# WT_ControlBoard.net
KiCad netlist of a schematic drawn in EAGLE
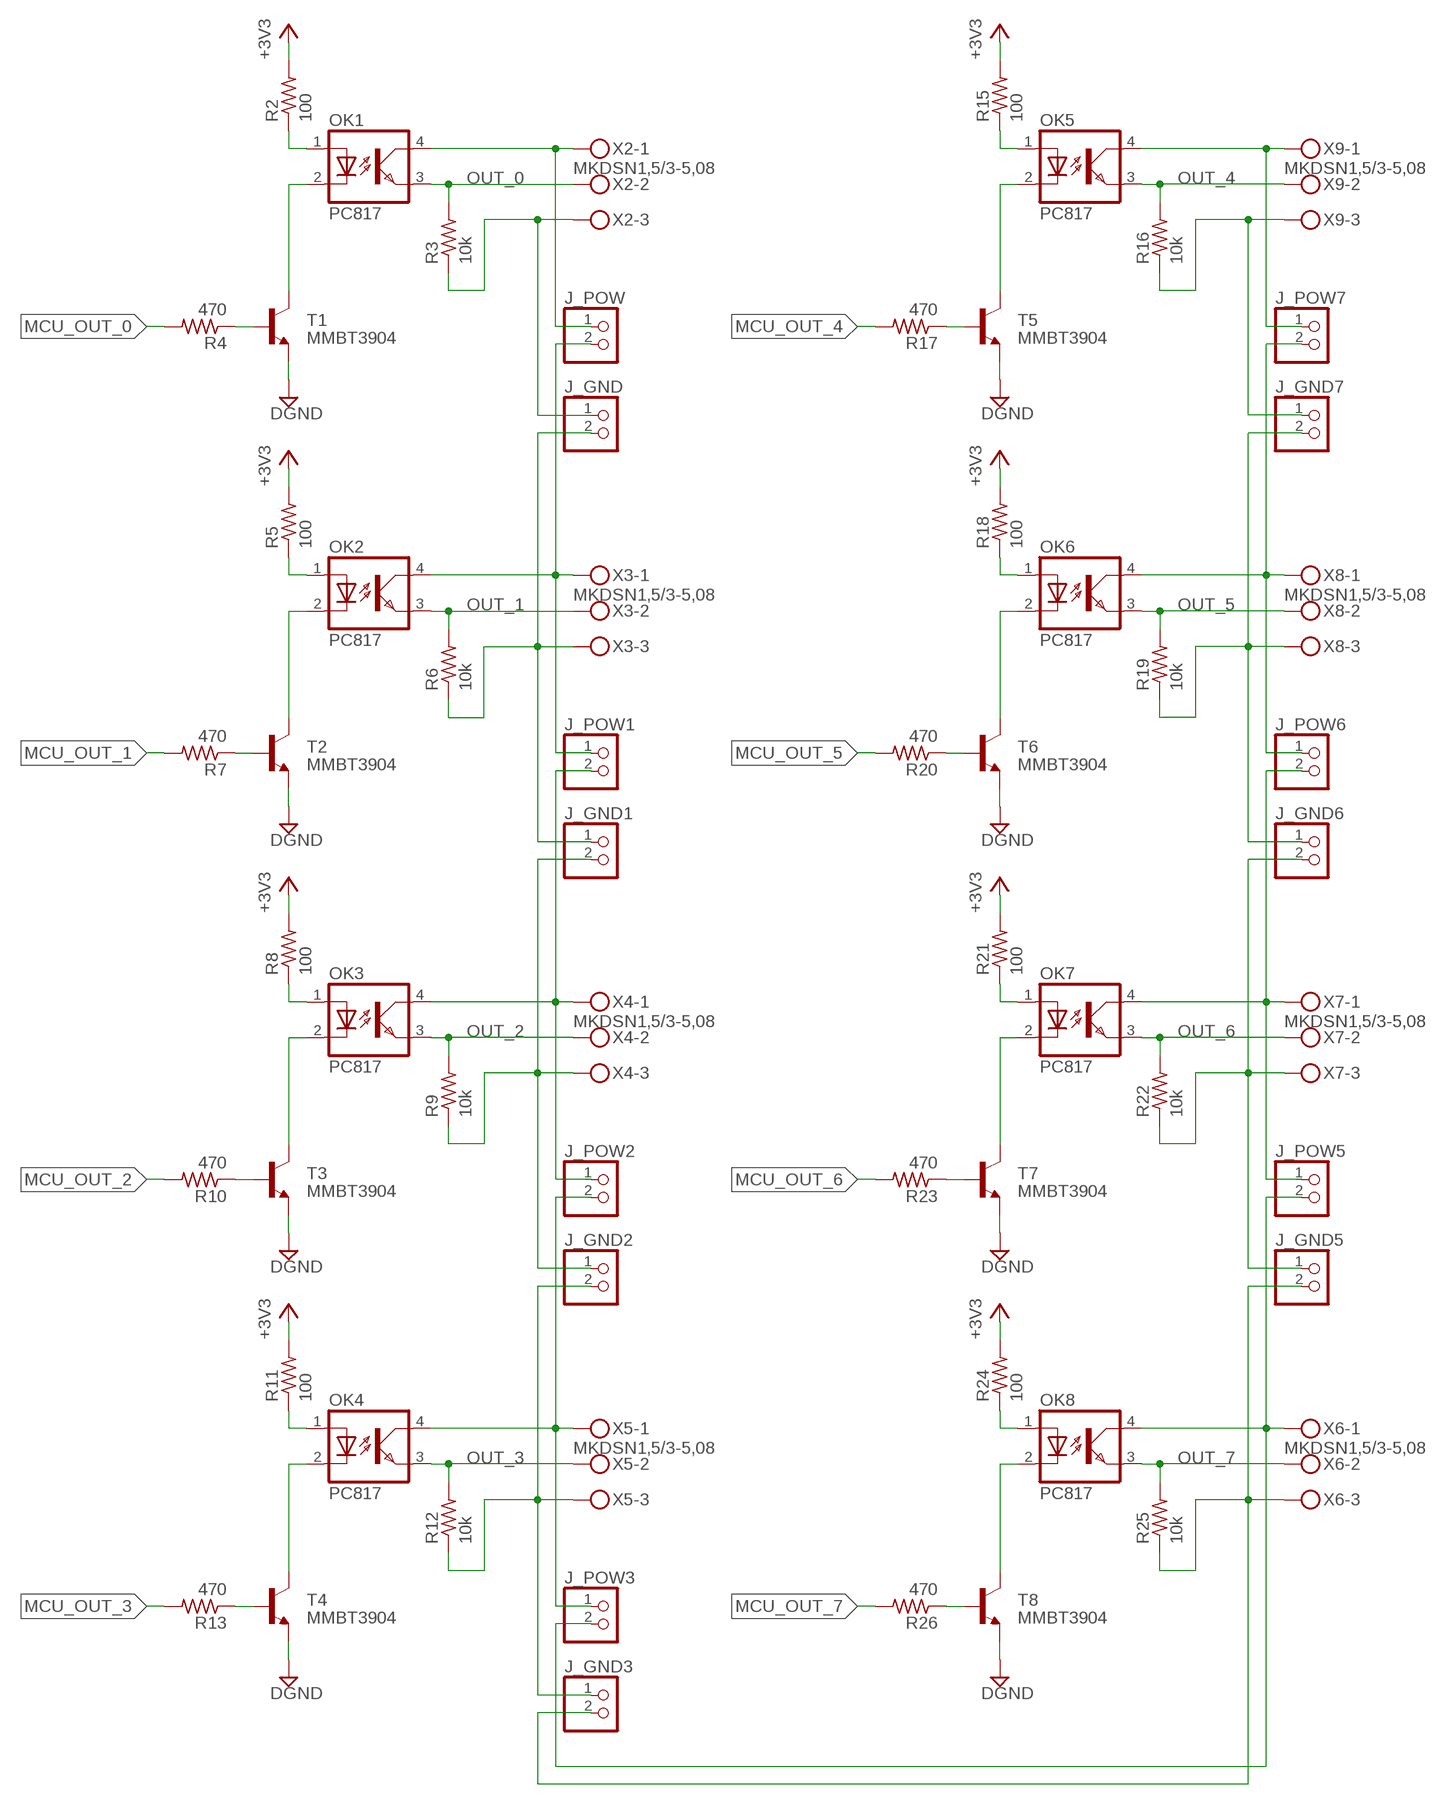
[diagram p0: schematic, sheet 1]
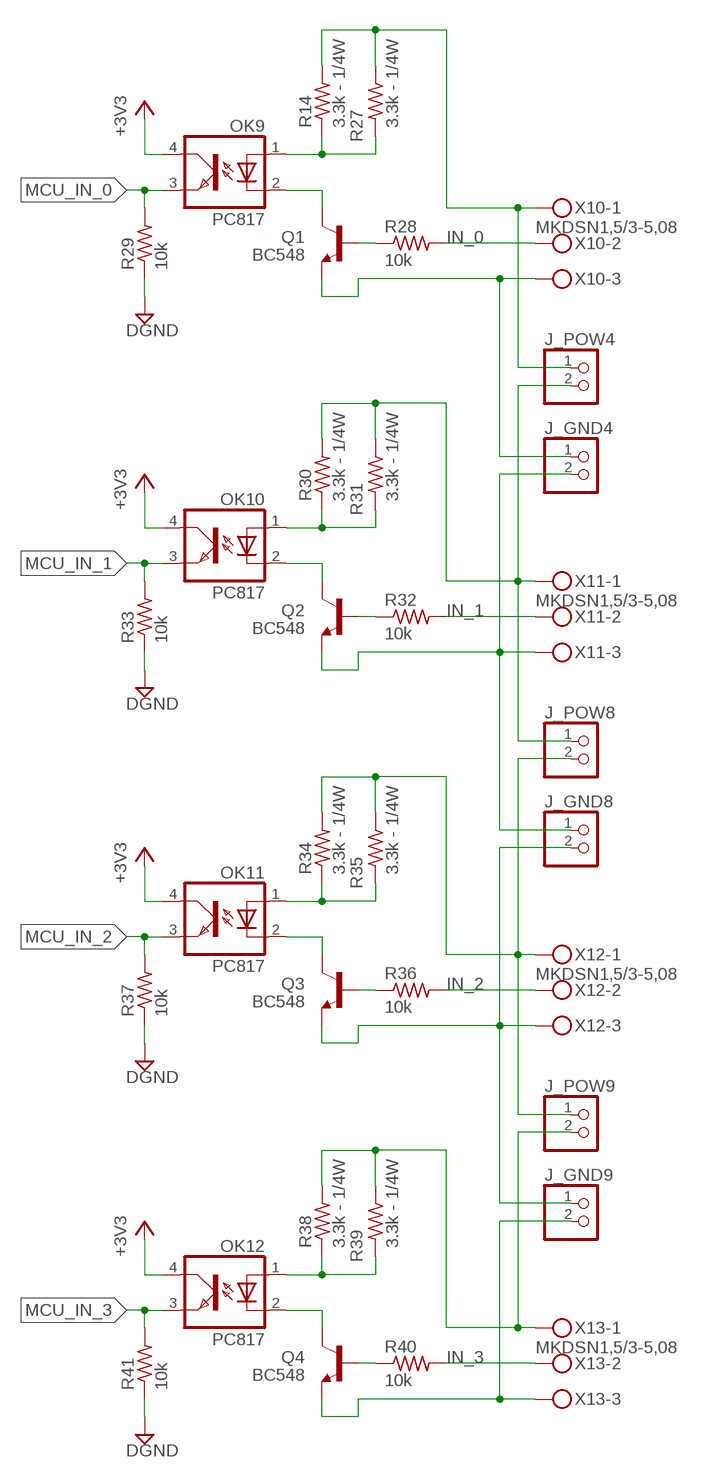
[diagram p1: schematic, sheet 2]
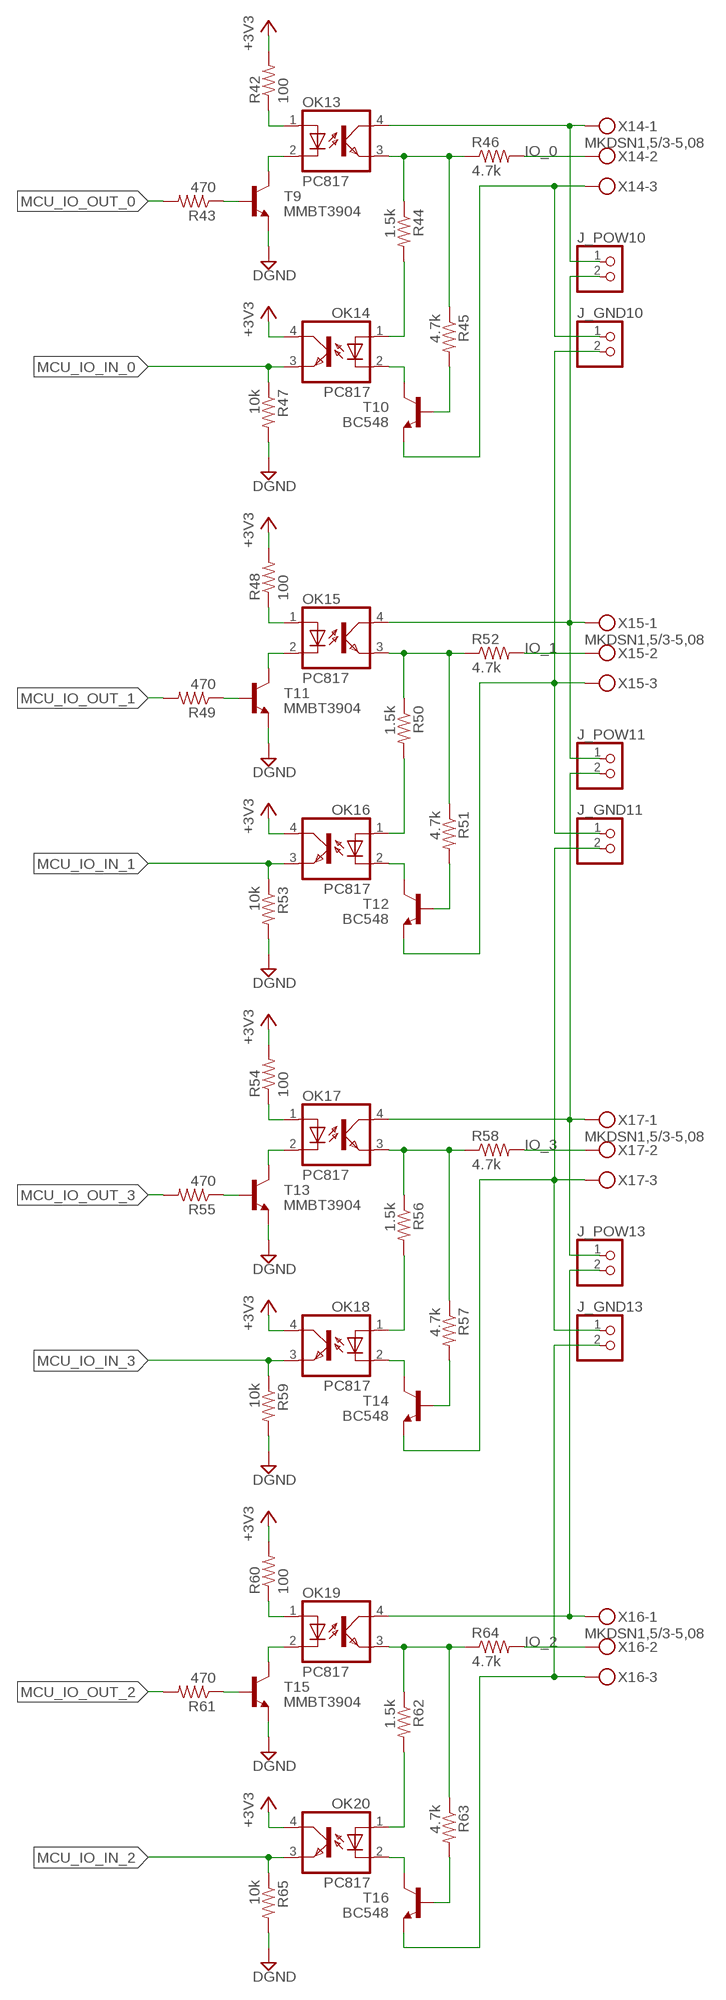
[diagram p2: schematic, sheet 3]
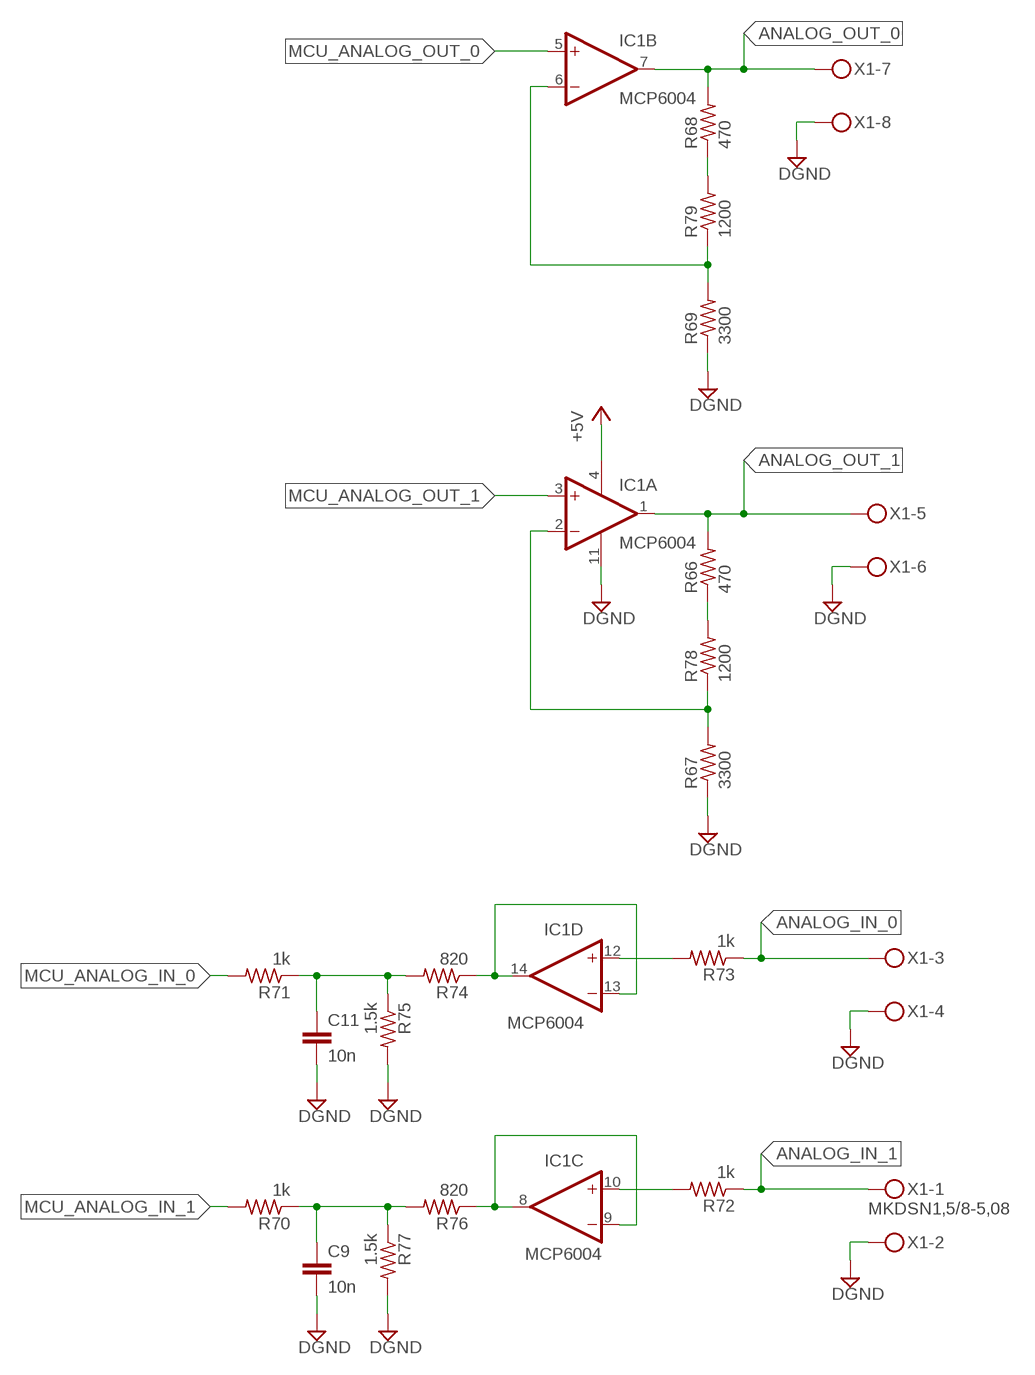
[diagram p3: schematic, sheet 4]
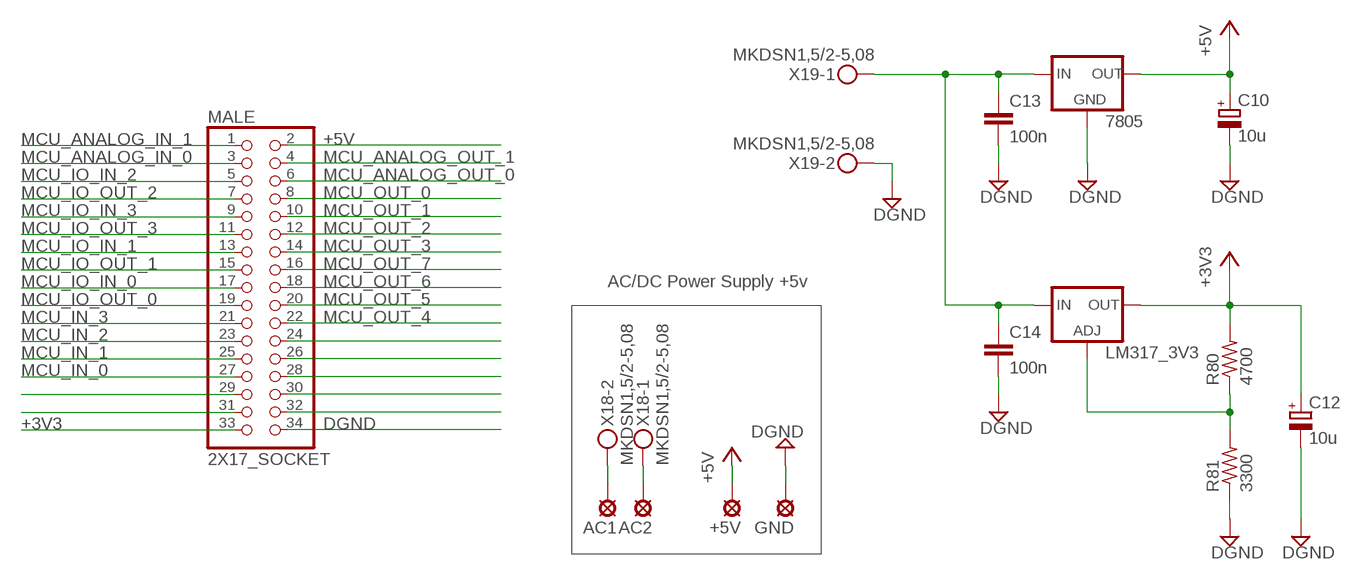
[diagram p4: schematic, sheet 5]

(export (version "E")
  (design (tool "Eeschema 10.0.6"))
  (components
    (comp (ref "+5V")
      (value "LSP10")
      (footprint "eagle-import:LSP10")
      (libsource (lib "eagle-import") (part "LSP10"))
    )
    (comp (ref "7805")
      (value "78XXS")
      (footprint "eagle-import:78XXS")
      (libsource (lib "eagle-import") (part "78XXS"))
    )
    (comp (ref "AC1")
      (value "LSP10")
      (footprint "eagle-import:LSP10")
      (libsource (lib "eagle-import") (part "LSP10"))
    )
    (comp (ref "AC2")
      (value "LSP10")
      (footprint "eagle-import:LSP10")
      (libsource (lib "eagle-import") (part "LSP10"))
    )
    (comp (ref "C10")
      (value "10u")
      (footprint "eagle-import:E1,8-4")
      (libsource (lib "eagle-import") (part "CPOL-EUE1.8-4"))
    )
    (comp (ref "C12")
      (value "10u")
      (footprint "eagle-import:E1,8-4")
      (libsource (lib "eagle-import") (part "CPOL-EUE1.8-4"))
    )
    (comp (ref "C13")
      (value "100n")
      (footprint "eagle-import:C1206")
      (libsource (lib "eagle-import") (part "C-EUC1206"))
    )
    (comp (ref "C14")
      (value "100n")
      (footprint "eagle-import:C1206")
      (libsource (lib "eagle-import") (part "C-EUC1206"))
    )
    (comp (ref "GND")
      (value "LSP10")
      (footprint "eagle-import:LSP10")
      (libsource (lib "eagle-import") (part "LSP10"))
    )
    (comp (ref "LM317_3V3")
      (value "LM317TS")
      (footprint "eagle-import:317TS")
      (libsource (lib "eagle-import") (part "LM317TS"))
    )
    (comp (ref "MALE")
      (value "2X17_SOCKET")
      (footprint "eagle-import:2X17_SOCKET")
      (libsource (lib "eagle-import") (part "2X17_SOCKET"))
    )
    (comp (ref "R80")
      (value "4700")
      (footprint "eagle-import:0204V")
      (libsource (lib "eagle-import") (part "R-US_0204/2V"))
    )
    (comp (ref "R81")
      (value "3300")
      (footprint "eagle-import:0204V")
      (libsource (lib "eagle-import") (part "R-US_0204/2V"))
    )
    (comp (ref "X18")
      (value "MKDSN1,5/2-5,08")
      (footprint "eagle-import:MKDSN1,5_2-5,08")
      (libsource (lib "eagle-import") (part "MKDSN1,5/2-5,08"))
    )
    (comp (ref "X19")
      (value "MKDSN1,5/2-5,08")
      (footprint "eagle-import:MKDSN1,5_2-5,08")
      (libsource (lib "eagle-import") (part "MKDSN1,5/2-5,08"))
    )
    (comp (ref "C9")
      (value "10n")
      (footprint "eagle-import:C0402")
      (libsource (lib "eagle-import") (part "C-EUC0402"))
    )
    (comp (ref "C11")
      (value "10n")
      (footprint "eagle-import:C0402")
      (libsource (lib "eagle-import") (part "C-EUC0402"))
    )
    (comp (ref "IC1")
      (value "MCP6004")
      (footprint "eagle-import:SO14")
      (libsource (lib "eagle-import") (part "LM324D"))
    )
    (comp (ref "R66")
      (value "470")
      (footprint "eagle-import:R0402")
      (libsource (lib "eagle-import") (part "R-US_R0402"))
    )
    (comp (ref "R67")
      (value "3300")
      (footprint "eagle-import:R0402")
      (libsource (lib "eagle-import") (part "R-US_R0402"))
    )
    (comp (ref "R68")
      (value "470")
      (footprint "eagle-import:R0402")
      (libsource (lib "eagle-import") (part "R-US_R0402"))
    )
    (comp (ref "R69")
      (value "3300")
      (footprint "eagle-import:R0402")
      (libsource (lib "eagle-import") (part "R-US_R0402"))
    )
    (comp (ref "R70")
      (value "1k")
      (footprint "eagle-import:R0402")
      (libsource (lib "eagle-import") (part "R-US_R0402"))
    )
    (comp (ref "R71")
      (value "1k")
      (footprint "eagle-import:R0402")
      (libsource (lib "eagle-import") (part "R-US_R0402"))
    )
    (comp (ref "R72")
      (value "1k")
      (footprint "eagle-import:0204V")
      (libsource (lib "eagle-import") (part "R-US_0204/2V"))
    )
    (comp (ref "R73")
      (value "1k")
      (footprint "eagle-import:0204_7")
      (libsource (lib "eagle-import") (part "R-US_0204/7"))
    )
    (comp (ref "R74")
      (value "820")
      (footprint "eagle-import:R0402")
      (libsource (lib "eagle-import") (part "R-US_R0402"))
    )
    (comp (ref "R75")
      (value "1.5k")
      (footprint "eagle-import:R0402")
      (libsource (lib "eagle-import") (part "R-US_R0402"))
    )
    (comp (ref "R76")
      (value "820")
      (footprint "eagle-import:R0402")
      (libsource (lib "eagle-import") (part "R-US_R0402"))
    )
    (comp (ref "R77")
      (value "1.5k")
      (footprint "eagle-import:R0402")
      (libsource (lib "eagle-import") (part "R-US_R0402"))
    )
    (comp (ref "R78")
      (value "1200")
      (footprint "eagle-import:R0402")
      (libsource (lib "eagle-import") (part "R-US_R0402"))
    )
    (comp (ref "R79")
      (value "1200")
      (footprint "eagle-import:R0402")
      (libsource (lib "eagle-import") (part "R-US_R0402"))
    )
    (comp (ref "X1")
      (value "MKDSN1,5/8-5,08")
      (footprint "eagle-import:MKDSN1,5_8-5,08")
      (libsource (lib "eagle-import") (part "MKDSN1,5/8-5,08"))
    )
    (comp (ref "J_GND4")
      (value "PINHD-1X2")
      (footprint "eagle-import:1X02")
      (libsource (lib "eagle-import") (part "PINHD-1X2"))
    )
    (comp (ref "J_GND8")
      (value "PINHD-1X2")
      (footprint "eagle-import:1X02")
      (libsource (lib "eagle-import") (part "PINHD-1X2"))
    )
    (comp (ref "J_GND9")
      (value "PINHD-1X2")
      (footprint "eagle-import:1X02")
      (libsource (lib "eagle-import") (part "PINHD-1X2"))
    )
    (comp (ref "J_POW4")
      (value "PINHD-1X2")
      (footprint "eagle-import:1X02")
      (libsource (lib "eagle-import") (part "PINHD-1X2"))
    )
    (comp (ref "J_POW8")
      (value "PINHD-1X2")
      (footprint "eagle-import:1X02")
      (libsource (lib "eagle-import") (part "PINHD-1X2"))
    )
    (comp (ref "J_POW9")
      (value "PINHD-1X2")
      (footprint "eagle-import:1X02")
      (libsource (lib "eagle-import") (part "PINHD-1X2"))
    )
    (comp (ref "OK9")
      (value "PC817")
      (footprint "eagle-import:DIL04")
      (fields (field (name "MPN") "PC817X4J000F"))
      (libsource (lib "eagle-import") (part "PC817"))
    )
    (comp (ref "OK10")
      (value "PC817")
      (footprint "eagle-import:DIL04")
      (fields (field (name "MPN") "PC817X4J000F"))
      (libsource (lib "eagle-import") (part "PC817"))
    )
    (comp (ref "OK11")
      (value "PC817")
      (footprint "eagle-import:DIL04")
      (fields (field (name "MPN") "PC817X4J000F"))
      (libsource (lib "eagle-import") (part "PC817"))
    )
    (comp (ref "OK12")
      (value "PC817")
      (footprint "eagle-import:DIL04")
      (fields (field (name "MPN") "PC817X4J000F"))
      (libsource (lib "eagle-import") (part "PC817"))
    )
    (comp (ref "Q1")
      (value "BC548")
      (footprint "eagle-import:TO92-EBC")
      (libsource (lib "eagle-import") (part "BC548"))
    )
    (comp (ref "Q2")
      (value "BC548")
      (footprint "eagle-import:TO92-EBC")
      (libsource (lib "eagle-import") (part "BC548"))
    )
    (comp (ref "Q3")
      (value "BC548")
      (footprint "eagle-import:TO92-EBC")
      (libsource (lib "eagle-import") (part "BC548"))
    )
    (comp (ref "Q4")
      (value "BC548")
      (footprint "eagle-import:TO92-EBC")
      (libsource (lib "eagle-import") (part "BC548"))
    )
    (comp (ref "R14")
      (value "3.3k - 1/4W")
      (footprint "eagle-import:0204V")
      (libsource (lib "eagle-import") (part "R-US_0204/2V"))
    )
    (comp (ref "R27")
      (value "3.3k - 1/4W")
      (footprint "eagle-import:0204V")
      (libsource (lib "eagle-import") (part "R-US_0204/2V"))
    )
    (comp (ref "R28")
      (value "10k")
      (footprint "eagle-import:0204_5")
      (libsource (lib "eagle-import") (part "R-US_0204/5"))
    )
    (comp (ref "R29")
      (value "10k")
      (footprint "eagle-import:R0402")
      (libsource (lib "eagle-import") (part "R-US_R0402"))
    )
    (comp (ref "R30")
      (value "3.3k - 1/4W")
      (footprint "eagle-import:0204V")
      (libsource (lib "eagle-import") (part "R-US_0204/2V"))
    )
    (comp (ref "R31")
      (value "3.3k - 1/4W")
      (footprint "eagle-import:0204V")
      (libsource (lib "eagle-import") (part "R-US_0204/2V"))
    )
    (comp (ref "R32")
      (value "10k")
      (footprint "eagle-import:0204_5")
      (libsource (lib "eagle-import") (part "R-US_0204/5"))
    )
    (comp (ref "R33")
      (value "10k")
      (footprint "eagle-import:R0402")
      (libsource (lib "eagle-import") (part "R-US_R0402"))
    )
    (comp (ref "R34")
      (value "3.3k - 1/4W")
      (footprint "eagle-import:0204V")
      (libsource (lib "eagle-import") (part "R-US_0204/2V"))
    )
    (comp (ref "R35")
      (value "3.3k - 1/4W")
      (footprint "eagle-import:0204V")
      (libsource (lib "eagle-import") (part "R-US_0204/2V"))
    )
    (comp (ref "R36")
      (value "10k")
      (footprint "eagle-import:0204_5")
      (libsource (lib "eagle-import") (part "R-US_0204/5"))
    )
    (comp (ref "R37")
      (value "10k")
      (footprint "eagle-import:R0402")
      (libsource (lib "eagle-import") (part "R-US_R0402"))
    )
    (comp (ref "R38")
      (value "3.3k - 1/4W")
      (footprint "eagle-import:0204V")
      (libsource (lib "eagle-import") (part "R-US_0204/2V"))
    )
    (comp (ref "R39")
      (value "3.3k - 1/4W")
      (footprint "eagle-import:0204V")
      (libsource (lib "eagle-import") (part "R-US_0204/2V"))
    )
    (comp (ref "R40")
      (value "10k")
      (footprint "eagle-import:0204_5")
      (libsource (lib "eagle-import") (part "R-US_0204/5"))
    )
    (comp (ref "R41")
      (value "10k")
      (footprint "eagle-import:R0402")
      (libsource (lib "eagle-import") (part "R-US_R0402"))
    )
    (comp (ref "X10")
      (value "MKDSN1,5/3-5,08")
      (footprint "eagle-import:MKDSN1,5_3-5,08")
      (libsource (lib "eagle-import") (part "MKDSN1,5/3-5,08"))
    )
    (comp (ref "X11")
      (value "MKDSN1,5/3-5,08")
      (footprint "eagle-import:MKDSN1,5_3-5,08")
      (libsource (lib "eagle-import") (part "MKDSN1,5/3-5,08"))
    )
    (comp (ref "X12")
      (value "MKDSN1,5/3-5,08")
      (footprint "eagle-import:MKDSN1,5_3-5,08")
      (libsource (lib "eagle-import") (part "MKDSN1,5/3-5,08"))
    )
    (comp (ref "X13")
      (value "MKDSN1,5/3-5,08")
      (footprint "eagle-import:MKDSN1,5_3-5,08")
      (libsource (lib "eagle-import") (part "MKDSN1,5/3-5,08"))
    )
    (comp (ref "J_GND")
      (value "PINHD-1X2")
      (footprint "eagle-import:1X02")
      (libsource (lib "eagle-import") (part "PINHD-1X2"))
    )
    (comp (ref "J_GND1")
      (value "PINHD-1X2")
      (footprint "eagle-import:1X02")
      (libsource (lib "eagle-import") (part "PINHD-1X2"))
    )
    (comp (ref "J_GND2")
      (value "PINHD-1X2")
      (footprint "eagle-import:1X02")
      (libsource (lib "eagle-import") (part "PINHD-1X2"))
    )
    (comp (ref "J_GND3")
      (value "PINHD-1X2")
      (footprint "eagle-import:1X02")
      (libsource (lib "eagle-import") (part "PINHD-1X2"))
    )
    (comp (ref "J_GND5")
      (value "PINHD-1X2")
      (footprint "eagle-import:1X02")
      (libsource (lib "eagle-import") (part "PINHD-1X2"))
    )
    (comp (ref "J_GND6")
      (value "PINHD-1X2")
      (footprint "eagle-import:1X02")
      (libsource (lib "eagle-import") (part "PINHD-1X2"))
    )
    (comp (ref "J_GND7")
      (value "PINHD-1X2")
      (footprint "eagle-import:1X02")
      (libsource (lib "eagle-import") (part "PINHD-1X2"))
    )
    (comp (ref "J_POW")
      (value "PINHD-1X2")
      (footprint "eagle-import:1X02")
      (libsource (lib "eagle-import") (part "PINHD-1X2"))
    )
    (comp (ref "J_POW1")
      (value "PINHD-1X2")
      (footprint "eagle-import:1X02")
      (libsource (lib "eagle-import") (part "PINHD-1X2"))
    )
    (comp (ref "J_POW2")
      (value "PINHD-1X2")
      (footprint "eagle-import:1X02")
      (libsource (lib "eagle-import") (part "PINHD-1X2"))
    )
    (comp (ref "J_POW3")
      (value "PINHD-1X2")
      (footprint "eagle-import:1X02")
      (libsource (lib "eagle-import") (part "PINHD-1X2"))
    )
    (comp (ref "J_POW5")
      (value "PINHD-1X2")
      (footprint "eagle-import:1X02")
      (libsource (lib "eagle-import") (part "PINHD-1X2"))
    )
    (comp (ref "J_POW6")
      (value "PINHD-1X2")
      (footprint "eagle-import:1X02")
      (libsource (lib "eagle-import") (part "PINHD-1X2"))
    )
    (comp (ref "J_POW7")
      (value "PINHD-1X2")
      (footprint "eagle-import:1X02")
      (libsource (lib "eagle-import") (part "PINHD-1X2"))
    )
    (comp (ref "OK1")
      (value "PC817")
      (footprint "eagle-import:DIL04")
      (fields (field (name "MPN") "PC817X4J000F"))
      (libsource (lib "eagle-import") (part "PC817"))
    )
    (comp (ref "OK2")
      (value "PC817")
      (footprint "eagle-import:DIL04")
      (fields (field (name "MPN") "PC817X4J000F"))
      (libsource (lib "eagle-import") (part "PC817"))
    )
    (comp (ref "OK3")
      (value "PC817")
      (footprint "eagle-import:DIL04")
      (fields (field (name "MPN") "PC817X4J000F"))
      (libsource (lib "eagle-import") (part "PC817"))
    )
    (comp (ref "OK4")
      (value "PC817")
      (footprint "eagle-import:DIL04")
      (fields (field (name "MPN") "PC817X4J000F"))
      (libsource (lib "eagle-import") (part "PC817"))
    )
    (comp (ref "OK5")
      (value "PC817")
      (footprint "eagle-import:DIL04")
      (fields (field (name "MPN") "PC817X4J000F"))
      (libsource (lib "eagle-import") (part "PC817"))
    )
    (comp (ref "OK6")
      (value "PC817")
      (footprint "eagle-import:DIL04")
      (fields (field (name "MPN") "PC817X4J000F"))
      (libsource (lib "eagle-import") (part "PC817"))
    )
    (comp (ref "OK7")
      (value "PC817")
      (footprint "eagle-import:DIL04")
      (fields (field (name "MPN") "PC817X4J000F"))
      (libsource (lib "eagle-import") (part "PC817"))
    )
    (comp (ref "OK8")
      (value "PC817")
      (footprint "eagle-import:DIL04")
      (fields (field (name "MPN") "PC817X4J000F"))
      (libsource (lib "eagle-import") (part "PC817"))
    )
    (comp (ref "R2")
      (value "100")
      (footprint "eagle-import:R0402")
      (libsource (lib "eagle-import") (part "R-US_R0402"))
    )
    (comp (ref "R3")
      (value "10k")
      (footprint "eagle-import:R0402")
      (libsource (lib "eagle-import") (part "R-US_R0402"))
    )
    (comp (ref "R4")
      (value "470")
      (footprint "eagle-import:0204_5")
      (libsource (lib "eagle-import") (part "R-US_0204/5"))
    )
    (comp (ref "R5")
      (value "100")
      (footprint "eagle-import:R0402")
      (libsource (lib "eagle-import") (part "R-US_R0402"))
    )
    (comp (ref "R6")
      (value "10k")
      (footprint "eagle-import:R0402")
      (libsource (lib "eagle-import") (part "R-US_R0402"))
    )
    (comp (ref "R7")
      (value "470")
      (footprint "eagle-import:0204_5")
      (libsource (lib "eagle-import") (part "R-US_0204/5"))
    )
    (comp (ref "R8")
      (value "100")
      (footprint "eagle-import:R0402")
      (libsource (lib "eagle-import") (part "R-US_R0402"))
    )
    (comp (ref "R9")
      (value "10k")
      (footprint "eagle-import:R0402")
      (libsource (lib "eagle-import") (part "R-US_R0402"))
    )
    (comp (ref "R10")
      (value "470")
      (footprint "eagle-import:0204_5")
      (libsource (lib "eagle-import") (part "R-US_0204/5"))
    )
    (comp (ref "R11")
      (value "100")
      (footprint "eagle-import:R0402")
      (libsource (lib "eagle-import") (part "R-US_R0402"))
    )
    (comp (ref "R12")
      (value "10k")
      (footprint "eagle-import:R0402")
      (libsource (lib "eagle-import") (part "R-US_R0402"))
    )
    (comp (ref "R13")
      (value "470")
      (footprint "eagle-import:0204_5")
      (libsource (lib "eagle-import") (part "R-US_0204/5"))
    )
    (comp (ref "R15")
      (value "100")
      (footprint "eagle-import:R0402")
      (libsource (lib "eagle-import") (part "R-US_R0402"))
    )
    (comp (ref "R16")
      (value "10k")
      (footprint "eagle-import:R0402")
      (libsource (lib "eagle-import") (part "R-US_R0402"))
    )
    (comp (ref "R17")
      (value "470")
      (footprint "eagle-import:0204_7")
      (libsource (lib "eagle-import") (part "R-US_0204/7"))
    )
    (comp (ref "R18")
      (value "100")
      (footprint "eagle-import:R0402")
      (libsource (lib "eagle-import") (part "R-US_R0402"))
    )
    (comp (ref "R19")
      (value "10k")
      (footprint "eagle-import:R0402")
      (libsource (lib "eagle-import") (part "R-US_R0402"))
    )
    (comp (ref "R20")
      (value "470")
      (footprint "eagle-import:0204_5")
      (libsource (lib "eagle-import") (part "R-US_0204/5"))
    )
    (comp (ref "R21")
      (value "100")
      (footprint "eagle-import:R0402")
      (libsource (lib "eagle-import") (part "R-US_R0402"))
    )
    (comp (ref "R22")
      (value "10k")
      (footprint "eagle-import:R0402")
      (libsource (lib "eagle-import") (part "R-US_R0402"))
    )
    (comp (ref "R23")
      (value "470")
      (footprint "eagle-import:0204_5")
      (libsource (lib "eagle-import") (part "R-US_0204/5"))
    )
    (comp (ref "R24")
      (value "100")
      (footprint "eagle-import:R0402")
      (libsource (lib "eagle-import") (part "R-US_R0402"))
    )
    (comp (ref "R25")
      (value "10k")
      (footprint "eagle-import:R0402")
      (libsource (lib "eagle-import") (part "R-US_R0402"))
    )
    (comp (ref "R26")
      (value "470")
      (footprint "eagle-import:0204_5")
      (libsource (lib "eagle-import") (part "R-US_0204/5"))
    )
    (comp (ref "T1")
      (value "MMBT3904")
      (footprint "eagle-import:SOT23-BEC")
      (libsource (lib "eagle-import") (part "-NPN-SOT23-BECMMBT3904LT1"))
    )
    (comp (ref "T2")
      (value "MMBT3904")
      (footprint "eagle-import:SOT23-BEC")
      (libsource (lib "eagle-import") (part "-NPN-SOT23-BECMMBT3904LT1"))
    )
    (comp (ref "T3")
      (value "MMBT3904")
      (footprint "eagle-import:SOT23-BEC")
      (libsource (lib "eagle-import") (part "-NPN-SOT23-BECMMBT3904LT1"))
    )
    (comp (ref "T4")
      (value "MMBT3904")
      (footprint "eagle-import:SOT23-BEC")
      (libsource (lib "eagle-import") (part "-NPN-SOT23-BECMMBT3904LT1"))
    )
    (comp (ref "T5")
      (value "MMBT3904")
      (footprint "eagle-import:SOT23-BEC")
      (libsource (lib "eagle-import") (part "-NPN-SOT23-BECMMBT3904LT1"))
    )
    (comp (ref "T6")
      (value "MMBT3904")
      (footprint "eagle-import:SOT23-BEC")
      (libsource (lib "eagle-import") (part "-NPN-SOT23-BECMMBT3904LT1"))
    )
    (comp (ref "T7")
      (value "MMBT3904")
      (footprint "eagle-import:SOT23-BEC")
      (libsource (lib "eagle-import") (part "-NPN-SOT23-BECMMBT3904LT1"))
    )
    (comp (ref "T8")
      (value "MMBT3904")
      (footprint "eagle-import:SOT23-BEC")
      (libsource (lib "eagle-import") (part "-NPN-SOT23-BECMMBT3904LT1"))
    )
    (comp (ref "X2")
      (value "MKDSN1,5/3-5,08")
      (footprint "eagle-import:MKDSN1,5_3-5,08")
      (libsource (lib "eagle-import") (part "MKDSN1,5/3-5,08"))
    )
    (comp (ref "X3")
      (value "MKDSN1,5/3-5,08")
      (footprint "eagle-import:MKDSN1,5_3-5,08")
      (libsource (lib "eagle-import") (part "MKDSN1,5/3-5,08"))
    )
    (comp (ref "X4")
      (value "MKDSN1,5/3-5,08")
      (footprint "eagle-import:MKDSN1,5_3-5,08")
      (libsource (lib "eagle-import") (part "MKDSN1,5/3-5,08"))
    )
    (comp (ref "X5")
      (value "MKDSN1,5/3-5,08")
      (footprint "eagle-import:MKDSN1,5_3-5,08")
      (libsource (lib "eagle-import") (part "MKDSN1,5/3-5,08"))
    )
    (comp (ref "X6")
      (value "MKDSN1,5/3-5,08")
      (footprint "eagle-import:MKDSN1,5_3-5,08")
      (libsource (lib "eagle-import") (part "MKDSN1,5/3-5,08"))
    )
    (comp (ref "X7")
      (value "MKDSN1,5/3-5,08")
      (footprint "eagle-import:MKDSN1,5_3-5,08")
      (libsource (lib "eagle-import") (part "MKDSN1,5/3-5,08"))
    )
    (comp (ref "X8")
      (value "MKDSN1,5/3-5,08")
      (footprint "eagle-import:MKDSN1,5_3-5,08")
      (libsource (lib "eagle-import") (part "MKDSN1,5/3-5,08"))
    )
    (comp (ref "X9")
      (value "MKDSN1,5/3-5,08")
      (footprint "eagle-import:MKDSN1,5_3-5,08")
      (libsource (lib "eagle-import") (part "MKDSN1,5/3-5,08"))
    )
    (comp (ref "J_GND10")
      (value "PINHD-1X2")
      (footprint "eagle-import:1X02")
      (libsource (lib "eagle-import") (part "PINHD-1X2"))
    )
    (comp (ref "J_GND11")
      (value "PINHD-1X2")
      (footprint "eagle-import:1X02")
      (libsource (lib "eagle-import") (part "PINHD-1X2"))
    )
    (comp (ref "J_GND13")
      (value "PINHD-1X2")
      (footprint "eagle-import:1X02")
      (libsource (lib "eagle-import") (part "PINHD-1X2"))
    )
    (comp (ref "J_POW10")
      (value "PINHD-1X2")
      (footprint "eagle-import:1X02")
      (libsource (lib "eagle-import") (part "PINHD-1X2"))
    )
    (comp (ref "J_POW11")
      (value "PINHD-1X2")
      (footprint "eagle-import:1X02")
      (libsource (lib "eagle-import") (part "PINHD-1X2"))
    )
    (comp (ref "J_POW13")
      (value "PINHD-1X2")
      (footprint "eagle-import:1X02")
      (libsource (lib "eagle-import") (part "PINHD-1X2"))
    )
    (comp (ref "OK13")
      (value "PC817")
      (footprint "eagle-import:DIL04")
      (fields (field (name "MPN") "PC817X4J000F"))
      (libsource (lib "eagle-import") (part "PC817"))
    )
    (comp (ref "OK14")
      (value "PC817")
      (footprint "eagle-import:DIL04")
      (fields (field (name "MPN") "PC817X4J000F"))
      (libsource (lib "eagle-import") (part "PC817"))
    )
    (comp (ref "OK15")
      (value "PC817")
      (footprint "eagle-import:DIL04")
      (fields (field (name "MPN") "PC817X4J000F"))
      (libsource (lib "eagle-import") (part "PC817"))
    )
    (comp (ref "OK16")
      (value "PC817")
      (footprint "eagle-import:DIL04")
      (fields (field (name "MPN") "PC817X4J000F"))
      (libsource (lib "eagle-import") (part "PC817"))
    )
    (comp (ref "OK17")
      (value "PC817")
      (footprint "eagle-import:DIL04")
      (fields (field (name "MPN") "PC817X4J000F"))
      (libsource (lib "eagle-import") (part "PC817"))
    )
    (comp (ref "OK18")
      (value "PC817")
      (footprint "eagle-import:DIL04")
      (fields (field (name "MPN") "PC817X4J000F"))
      (libsource (lib "eagle-import") (part "PC817"))
    )
    (comp (ref "OK19")
      (value "PC817")
      (footprint "eagle-import:DIL04")
      (fields (field (name "MPN") "PC817X4J000F"))
      (libsource (lib "eagle-import") (part "PC817"))
    )
    (comp (ref "OK20")
      (value "PC817")
      (footprint "eagle-import:DIL04")
      (fields (field (name "MPN") "PC817X4J000F"))
      (libsource (lib "eagle-import") (part "PC817"))
    )
    (comp (ref "R42")
      (value "100")
      (footprint "eagle-import:0204_7")
      (libsource (lib "eagle-import") (part "R-US_0204/7"))
    )
    (comp (ref "R43")
      (value "470")
      (footprint "eagle-import:R0402")
      (libsource (lib "eagle-import") (part "R-US_R0402"))
    )
    (comp (ref "R44")
      (value "1.5k")
      (footprint "eagle-import:0204_5")
      (libsource (lib "eagle-import") (part "R-US_0204/5"))
    )
    (comp (ref "R45")
      (value "4.7k")
      (footprint "eagle-import:0204V")
      (libsource (lib "eagle-import") (part "R-US_0204/2V"))
    )
    (comp (ref "R46")
      (value "4.7k")
      (footprint "eagle-import:0204V")
      (libsource (lib "eagle-import") (part "R-US_0204/2V"))
    )
    (comp (ref "R47")
      (value "10k")
      (footprint "eagle-import:0204_5")
      (libsource (lib "eagle-import") (part "R-US_0204/5"))
    )
    (comp (ref "R48")
      (value "100")
      (footprint "eagle-import:0204_7")
      (libsource (lib "eagle-import") (part "R-US_0204/7"))
    )
    (comp (ref "R49")
      (value "470")
      (footprint "eagle-import:R0402")
      (libsource (lib "eagle-import") (part "R-US_R0402"))
    )
    (comp (ref "R50")
      (value "1.5k")
      (footprint "eagle-import:0204_5")
      (libsource (lib "eagle-import") (part "R-US_0204/5"))
    )
    (comp (ref "R51")
      (value "4.7k")
      (footprint "eagle-import:0204V")
      (libsource (lib "eagle-import") (part "R-US_0204/2V"))
    )
    (comp (ref "R52")
      (value "4.7k")
      (footprint "eagle-import:0204V")
      (libsource (lib "eagle-import") (part "R-US_0204/2V"))
    )
    (comp (ref "R53")
      (value "10k")
      (footprint "eagle-import:0204_5")
      (libsource (lib "eagle-import") (part "R-US_0204/5"))
    )
    (comp (ref "R54")
      (value "100")
      (footprint "eagle-import:0204_7")
      (libsource (lib "eagle-import") (part "R-US_0204/7"))
    )
    (comp (ref "R55")
      (value "470")
      (footprint "eagle-import:R0402")
      (libsource (lib "eagle-import") (part "R-US_R0402"))
    )
    (comp (ref "R56")
      (value "1.5k")
      (footprint "eagle-import:0204_5")
      (libsource (lib "eagle-import") (part "R-US_0204/5"))
    )
    (comp (ref "R57")
      (value "4.7k")
      (footprint "eagle-import:0204V")
      (libsource (lib "eagle-import") (part "R-US_0204/2V"))
    )
    (comp (ref "R58")
      (value "4.7k")
      (footprint "eagle-import:0204V")
      (libsource (lib "eagle-import") (part "R-US_0204/2V"))
    )
    (comp (ref "R59")
      (value "10k")
      (footprint "eagle-import:0204_5")
      (libsource (lib "eagle-import") (part "R-US_0204/5"))
    )
    (comp (ref "R60")
      (value "100")
      (footprint "eagle-import:0204_7")
      (libsource (lib "eagle-import") (part "R-US_0204/7"))
    )
    (comp (ref "R61")
      (value "470")
      (footprint "eagle-import:R0402")
      (libsource (lib "eagle-import") (part "R-US_R0402"))
    )
    (comp (ref "R62")
      (value "1.5k")
      (footprint "eagle-import:0204_5")
      (libsource (lib "eagle-import") (part "R-US_0204/5"))
    )
    (comp (ref "R63")
      (value "4.7k")
      (footprint "eagle-import:0204V")
      (libsource (lib "eagle-import") (part "R-US_0204/2V"))
    )
    (comp (ref "R64")
      (value "4.7k")
      (footprint "eagle-import:0204V")
      (libsource (lib "eagle-import") (part "R-US_0204/2V"))
    )
    (comp (ref "R65")
      (value "10k")
      (footprint "eagle-import:0204_5")
      (libsource (lib "eagle-import") (part "R-US_0204/5"))
    )
    (comp (ref "T9")
      (value "MMBT3904")
      (footprint "eagle-import:SOT23-BEC")
      (libsource (lib "eagle-import") (part "-NPN-SOT23-BECMMBT3904LT1"))
    )
    (comp (ref "T10")
      (value "BC548")
      (footprint "eagle-import:TO92-CBE")
      (libsource (lib "eagle-import") (part "-NPN-TO92-CBEBC548"))
    )
    (comp (ref "T11")
      (value "MMBT3904")
      (footprint "eagle-import:SOT23-BEC")
      (libsource (lib "eagle-import") (part "-NPN-SOT23-BECMMBT3904LT1"))
    )
    (comp (ref "T12")
      (value "BC548")
      (footprint "eagle-import:TO92-CBE")
      (libsource (lib "eagle-import") (part "-NPN-TO92-CBEBC548"))
    )
    (comp (ref "T13")
      (value "MMBT3904")
      (footprint "eagle-import:SOT23-BEC")
      (libsource (lib "eagle-import") (part "-NPN-SOT23-BECMMBT3904LT1"))
    )
    (comp (ref "T14")
      (value "BC548")
      (footprint "eagle-import:TO92-CBE")
      (libsource (lib "eagle-import") (part "-NPN-TO92-CBEBC548"))
    )
    (comp (ref "T15")
      (value "MMBT3904")
      (footprint "eagle-import:SOT23-BEC")
      (libsource (lib "eagle-import") (part "-NPN-SOT23-BECMMBT3904LT1"))
    )
    (comp (ref "T16")
      (value "BC548")
      (footprint "eagle-import:TO92-CBE")
      (libsource (lib "eagle-import") (part "-NPN-TO92-CBEBC548"))
    )
    (comp (ref "X14")
      (value "MKDSN1,5/3-5,08")
      (footprint "eagle-import:MKDSN1,5_3-5,08")
      (libsource (lib "eagle-import") (part "MKDSN1,5/3-5,08"))
    )
    (comp (ref "X15")
      (value "MKDSN1,5/3-5,08")
      (footprint "eagle-import:MKDSN1,5_3-5,08")
      (libsource (lib "eagle-import") (part "MKDSN1,5/3-5,08"))
    )
    (comp (ref "X16")
      (value "MKDSN1,5/3-5,08")
      (footprint "eagle-import:MKDSN1,5_3-5,08")
      (libsource (lib "eagle-import") (part "MKDSN1,5/3-5,08"))
    )
    (comp (ref "X17")
      (value "MKDSN1,5/3-5,08")
      (footprint "eagle-import:MKDSN1,5_3-5,08")
      (libsource (lib "eagle-import") (part "MKDSN1,5/3-5,08"))
    )
  )
  (nets
    (net (code "1") (name "+3V3") (class "Default")
      (node (ref "C12") (pin "+") (pinfunction "+_+") (pintype "passive"))
      (node (ref "LM317_3V3") (pin "2") (pinfunction "OUT_2") (pintype "passive"))
      (node (ref "MALE") (pin "33") (pinfunction "33_33") (pintype "passive"))
      (node (ref "OK10") (pin "4") (pinfunction "COL_4") (pintype "passive"))
      (node (ref "OK11") (pin "4") (pinfunction "COL_4") (pintype "passive"))
      (node (ref "OK12") (pin "4") (pinfunction "COL_4") (pintype "passive"))
      (node (ref "OK14") (pin "4") (pinfunction "COL_4") (pintype "passive"))
      (node (ref "OK16") (pin "4") (pinfunction "COL_4") (pintype "passive"))
      (node (ref "OK18") (pin "4") (pinfunction "COL_4") (pintype "passive"))
      (node (ref "OK20") (pin "4") (pinfunction "COL_4") (pintype "passive"))
      (node (ref "OK9") (pin "4") (pinfunction "COL_4") (pintype "passive"))
      (node (ref "R11") (pin "2") (pinfunction "2_2") (pintype "passive"))
      (node (ref "R15") (pin "2") (pinfunction "2_2") (pintype "passive"))
      (node (ref "R18") (pin "2") (pinfunction "2_2") (pintype "passive"))
      (node (ref "R2") (pin "2") (pinfunction "2_2") (pintype "passive"))
      (node (ref "R21") (pin "2") (pinfunction "2_2") (pintype "passive"))
      (node (ref "R24") (pin "2") (pinfunction "2_2") (pintype "passive"))
      (node (ref "R42") (pin "2") (pinfunction "2_2") (pintype "passive"))
      (node (ref "R48") (pin "2") (pinfunction "2_2") (pintype "passive"))
      (node (ref "R5") (pin "2") (pinfunction "2_2") (pintype "passive"))
      (node (ref "R54") (pin "2") (pinfunction "2_2") (pintype "passive"))
      (node (ref "R60") (pin "2") (pinfunction "2_2") (pintype "passive"))
      (node (ref "R8") (pin "2") (pinfunction "2_2") (pintype "passive"))
      (node (ref "R80") (pin "2") (pinfunction "2_2") (pintype "passive"))
    )
    (net (code "2") (name "+5V") (class "Default")
      (node (ref "+5V") (pin "MP") (pinfunction "MP_MP") (pintype "passive"))
      (node (ref "7805") (pin "OUT") (pinfunction "OUT_OUT") (pintype "passive"))
      (node (ref "C10") (pin "+") (pinfunction "+_+") (pintype "passive"))
      (node (ref "IC1") (pin "4") (pinfunction "V+_4") (pintype "power_in"))
      (node (ref "MALE") (pin "2") (pinfunction "2_2") (pintype "passive"))
    )
    (net (code "3") (name "ANALOG_IN_0") (class "Default")
      (node (ref "R73") (pin "1") (pinfunction "1_1") (pintype "passive"))
      (node (ref "X1") (pin "3") (pinfunction "KL_3") (pintype "passive"))
    )
    (net (code "4") (name "ANALOG_IN_1") (class "Default")
      (node (ref "R72") (pin "1") (pinfunction "1_1") (pintype "passive"))
      (node (ref "X1") (pin "1") (pinfunction "KL_1") (pintype "passive"))
    )
    (net (code "5") (name "ANALOG_OUT_0") (class "Default")
      (node (ref "IC1") (pin "7") (pinfunction "OUT_7") (pintype "output"))
      (node (ref "R68") (pin "2") (pinfunction "2_2") (pintype "passive"))
      (node (ref "X1") (pin "7") (pinfunction "KL_7") (pintype "passive"))
    )
    (net (code "6") (name "ANALOG_OUT_1") (class "Default")
      (node (ref "IC1") (pin "1") (pinfunction "OUT_1") (pintype "output"))
      (node (ref "R66") (pin "2") (pinfunction "2_2") (pintype "passive"))
      (node (ref "X1") (pin "5") (pinfunction "KL_5") (pintype "passive"))
    )
    (net (code "7") (name "DGND") (class "Default")
      (node (ref "7805") (pin "GND") (pinfunction "GND_GND") (pintype "input"))
      (node (ref "C10") (pin "-") (pinfunction "-_-") (pintype "passive"))
      (node (ref "C11") (pin "2") (pinfunction "2_2") (pintype "passive"))
      (node (ref "C12") (pin "-") (pinfunction "-_-") (pintype "passive"))
      (node (ref "C13") (pin "2") (pinfunction "2_2") (pintype "passive"))
      (node (ref "C14") (pin "2") (pinfunction "2_2") (pintype "passive"))
      (node (ref "C9") (pin "2") (pinfunction "2_2") (pintype "passive"))
      (node (ref "GND") (pin "MP") (pinfunction "MP_MP") (pintype "passive"))
      (node (ref "IC1") (pin "11") (pinfunction "V-_11") (pintype "power_in"))
      (node (ref "MALE") (pin "34") (pinfunction "34_34") (pintype "passive"))
      (node (ref "R29") (pin "1") (pinfunction "1_1") (pintype "passive"))
      (node (ref "R33") (pin "1") (pinfunction "1_1") (pintype "passive"))
      (node (ref "R37") (pin "1") (pinfunction "1_1") (pintype "passive"))
      (node (ref "R41") (pin "1") (pinfunction "1_1") (pintype "passive"))
      (node (ref "R47") (pin "2") (pinfunction "2_2") (pintype "passive"))
      (node (ref "R53") (pin "2") (pinfunction "2_2") (pintype "passive"))
      (node (ref "R59") (pin "2") (pinfunction "2_2") (pintype "passive"))
      (node (ref "R65") (pin "2") (pinfunction "2_2") (pintype "passive"))
      (node (ref "R67") (pin "1") (pinfunction "1_1") (pintype "passive"))
      (node (ref "R69") (pin "1") (pinfunction "1_1") (pintype "passive"))
      (node (ref "R75") (pin "2") (pinfunction "2_2") (pintype "passive"))
      (node (ref "R77") (pin "2") (pinfunction "2_2") (pintype "passive"))
      (node (ref "R81") (pin "1") (pinfunction "1_1") (pintype "passive"))
      (node (ref "T1") (pin "E") (pinfunction "E_E") (pintype "passive"))
      (node (ref "T11") (pin "E") (pinfunction "E_E") (pintype "passive"))
      (node (ref "T13") (pin "E") (pinfunction "E_E") (pintype "passive"))
      (node (ref "T15") (pin "E") (pinfunction "E_E") (pintype "passive"))
      (node (ref "T2") (pin "E") (pinfunction "E_E") (pintype "passive"))
      (node (ref "T3") (pin "E") (pinfunction "E_E") (pintype "passive"))
      (node (ref "T4") (pin "E") (pinfunction "E_E") (pintype "passive"))
      (node (ref "T5") (pin "E") (pinfunction "E_E") (pintype "passive"))
      (node (ref "T6") (pin "E") (pinfunction "E_E") (pintype "passive"))
      (node (ref "T7") (pin "E") (pinfunction "E_E") (pintype "passive"))
      (node (ref "T8") (pin "E") (pinfunction "E_E") (pintype "passive"))
      (node (ref "T9") (pin "E") (pinfunction "E_E") (pintype "passive"))
      (node (ref "X1") (pin "2") (pinfunction "KL_2") (pintype "passive"))
      (node (ref "X1") (pin "4") (pinfunction "KL_4") (pintype "passive"))
      (node (ref "X1") (pin "6") (pinfunction "KL_6") (pintype "passive"))
      (node (ref "X1") (pin "8") (pinfunction "KL_8") (pintype "passive"))
      (node (ref "X19") (pin "2") (pinfunction "KL_2") (pintype "passive"))
    )
    (net (code "8") (name "IN_0") (class "Default")
      (node (ref "R28") (pin "2") (pinfunction "2_2") (pintype "passive"))
      (node (ref "X10") (pin "2") (pinfunction "KL_2") (pintype "passive"))
    )
    (net (code "9") (name "IN_1") (class "Default")
      (node (ref "R32") (pin "2") (pinfunction "2_2") (pintype "passive"))
      (node (ref "X11") (pin "2") (pinfunction "KL_2") (pintype "passive"))
    )
    (net (code "10") (name "IN_2") (class "Default")
      (node (ref "R36") (pin "2") (pinfunction "2_2") (pintype "passive"))
      (node (ref "X12") (pin "2") (pinfunction "KL_2") (pintype "passive"))
    )
    (net (code "11") (name "IN_3") (class "Default")
      (node (ref "R40") (pin "2") (pinfunction "2_2") (pintype "passive"))
      (node (ref "X13") (pin "2") (pinfunction "KL_2") (pintype "passive"))
    )
    (net (code "12") (name "IO_0") (class "Default")
      (node (ref "R46") (pin "2") (pinfunction "2_2") (pintype "passive"))
      (node (ref "X14") (pin "2") (pinfunction "KL_2") (pintype "passive"))
    )
    (net (code "13") (name "IO_1") (class "Default")
      (node (ref "R52") (pin "2") (pinfunction "2_2") (pintype "passive"))
      (node (ref "X15") (pin "2") (pinfunction "KL_2") (pintype "passive"))
    )
    (net (code "14") (name "IO_2") (class "Default")
      (node (ref "R64") (pin "2") (pinfunction "2_2") (pintype "passive"))
      (node (ref "X16") (pin "2") (pinfunction "KL_2") (pintype "passive"))
    )
    (net (code "15") (name "IO_3") (class "Default")
      (node (ref "R58") (pin "2") (pinfunction "2_2") (pintype "passive"))
      (node (ref "X17") (pin "2") (pinfunction "KL_2") (pintype "passive"))
    )
    (net (code "16") (name "MCU_ANALOG_IN_0") (class "Default")
      (node (ref "MALE") (pin "3") (pinfunction "3_3") (pintype "passive"))
      (node (ref "R71") (pin "2") (pinfunction "2_2") (pintype "passive"))
    )
    (net (code "17") (name "MCU_ANALOG_IN_1") (class "Default")
      (node (ref "MALE") (pin "1") (pinfunction "1_1") (pintype "passive"))
      (node (ref "R70") (pin "2") (pinfunction "2_2") (pintype "passive"))
    )
    (net (code "18") (name "MCU_ANALOG_OUT_0") (class "Default")
      (node (ref "IC1") (pin "5") (pinfunction "+IN_5") (pintype "input"))
      (node (ref "MALE") (pin "6") (pinfunction "6_6") (pintype "passive"))
    )
    (net (code "19") (name "MCU_ANALOG_OUT_1") (class "Default")
      (node (ref "IC1") (pin "3") (pinfunction "+IN_3") (pintype "input"))
      (node (ref "MALE") (pin "4") (pinfunction "4_4") (pintype "passive"))
    )
    (net (code "20") (name "MCU_IN_0") (class "Default")
      (node (ref "MALE") (pin "27") (pinfunction "27_27") (pintype "passive"))
      (node (ref "OK9") (pin "3") (pinfunction "EMIT_3") (pintype "passive"))
      (node (ref "R29") (pin "2") (pinfunction "2_2") (pintype "passive"))
    )
    (net (code "21") (name "MCU_IN_1") (class "Default")
      (node (ref "MALE") (pin "25") (pinfunction "25_25") (pintype "passive"))
      (node (ref "OK10") (pin "3") (pinfunction "EMIT_3") (pintype "passive"))
      (node (ref "R33") (pin "2") (pinfunction "2_2") (pintype "passive"))
    )
    (net (code "22") (name "MCU_IN_2") (class "Default")
      (node (ref "MALE") (pin "23") (pinfunction "23_23") (pintype "passive"))
      (node (ref "OK11") (pin "3") (pinfunction "EMIT_3") (pintype "passive"))
      (node (ref "R37") (pin "2") (pinfunction "2_2") (pintype "passive"))
    )
    (net (code "23") (name "MCU_IN_3") (class "Default")
      (node (ref "MALE") (pin "21") (pinfunction "21_21") (pintype "passive"))
      (node (ref "OK12") (pin "3") (pinfunction "EMIT_3") (pintype "passive"))
      (node (ref "R41") (pin "2") (pinfunction "2_2") (pintype "passive"))
    )
    (net (code "24") (name "MCU_IO_IN_0") (class "Default")
      (node (ref "MALE") (pin "17") (pinfunction "17_17") (pintype "passive"))
      (node (ref "OK14") (pin "3") (pinfunction "EMIT_3") (pintype "passive"))
      (node (ref "R47") (pin "1") (pinfunction "1_1") (pintype "passive"))
    )
    (net (code "25") (name "MCU_IO_IN_1") (class "Default")
      (node (ref "MALE") (pin "13") (pinfunction "13_13") (pintype "passive"))
      (node (ref "OK16") (pin "3") (pinfunction "EMIT_3") (pintype "passive"))
      (node (ref "R53") (pin "1") (pinfunction "1_1") (pintype "passive"))
    )
    (net (code "26") (name "MCU_IO_IN_2") (class "Default")
      (node (ref "MALE") (pin "5") (pinfunction "5_5") (pintype "passive"))
      (node (ref "OK20") (pin "3") (pinfunction "EMIT_3") (pintype "passive"))
      (node (ref "R65") (pin "1") (pinfunction "1_1") (pintype "passive"))
    )
    (net (code "27") (name "MCU_IO_IN_3") (class "Default")
      (node (ref "MALE") (pin "9") (pinfunction "9_9") (pintype "passive"))
      (node (ref "OK18") (pin "3") (pinfunction "EMIT_3") (pintype "passive"))
      (node (ref "R59") (pin "1") (pinfunction "1_1") (pintype "passive"))
    )
    (net (code "28") (name "MCU_IO_OUT_0") (class "Default")
      (node (ref "MALE") (pin "19") (pinfunction "19_19") (pintype "passive"))
      (node (ref "R43") (pin "2") (pinfunction "2_2") (pintype "passive"))
    )
    (net (code "29") (name "MCU_IO_OUT_1") (class "Default")
      (node (ref "MALE") (pin "15") (pinfunction "15_15") (pintype "passive"))
      (node (ref "R49") (pin "2") (pinfunction "2_2") (pintype "passive"))
    )
    (net (code "30") (name "MCU_IO_OUT_2") (class "Default")
      (node (ref "MALE") (pin "7") (pinfunction "7_7") (pintype "passive"))
      (node (ref "R61") (pin "2") (pinfunction "2_2") (pintype "passive"))
    )
    (net (code "31") (name "MCU_IO_OUT_3") (class "Default")
      (node (ref "MALE") (pin "11") (pinfunction "11_11") (pintype "passive"))
      (node (ref "R55") (pin "2") (pinfunction "2_2") (pintype "passive"))
    )
    (net (code "32") (name "MCU_OUT_0") (class "Default")
      (node (ref "MALE") (pin "8") (pinfunction "8_8") (pintype "passive"))
      (node (ref "R4") (pin "2") (pinfunction "2_2") (pintype "passive"))
    )
    (net (code "33") (name "MCU_OUT_1") (class "Default")
      (node (ref "MALE") (pin "10") (pinfunction "10_10") (pintype "passive"))
      (node (ref "R7") (pin "2") (pinfunction "2_2") (pintype "passive"))
    )
    (net (code "34") (name "MCU_OUT_2") (class "Default")
      (node (ref "MALE") (pin "12") (pinfunction "12_12") (pintype "passive"))
      (node (ref "R10") (pin "2") (pinfunction "2_2") (pintype "passive"))
    )
    (net (code "35") (name "MCU_OUT_3") (class "Default")
      (node (ref "MALE") (pin "14") (pinfunction "14_14") (pintype "passive"))
      (node (ref "R13") (pin "2") (pinfunction "2_2") (pintype "passive"))
    )
    (net (code "36") (name "MCU_OUT_4") (class "Default")
      (node (ref "MALE") (pin "22") (pinfunction "22_22") (pintype "passive"))
      (node (ref "R17") (pin "2") (pinfunction "2_2") (pintype "passive"))
    )
    (net (code "37") (name "MCU_OUT_5") (class "Default")
      (node (ref "MALE") (pin "20") (pinfunction "20_20") (pintype "passive"))
      (node (ref "R20") (pin "2") (pinfunction "2_2") (pintype "passive"))
    )
    (net (code "38") (name "MCU_OUT_6") (class "Default")
      (node (ref "MALE") (pin "18") (pinfunction "18_18") (pintype "passive"))
      (node (ref "R23") (pin "2") (pinfunction "2_2") (pintype "passive"))
    )
    (net (code "39") (name "MCU_OUT_7") (class "Default")
      (node (ref "MALE") (pin "16") (pinfunction "16_16") (pintype "passive"))
      (node (ref "R26") (pin "2") (pinfunction "2_2") (pintype "passive"))
    )
    (net (code "40") (name "Net-(C9-Pad1)") (class "Default")
      (node (ref "C9") (pin "1") (pinfunction "1_1") (pintype "passive"))
      (node (ref "R70") (pin "1") (pinfunction "1_1") (pintype "passive"))
      (node (ref "R76") (pin "2") (pinfunction "2_2") (pintype "passive"))
      (node (ref "R77") (pin "1") (pinfunction "1_1") (pintype "passive"))
    )
    (net (code "41") (name "Net-(C11-Pad1)") (class "Default")
      (node (ref "C11") (pin "1") (pinfunction "1_1") (pintype "passive"))
      (node (ref "R71") (pin "1") (pinfunction "1_1") (pintype "passive"))
      (node (ref "R74") (pin "2") (pinfunction "2_2") (pintype "passive"))
      (node (ref "R75") (pin "1") (pinfunction "1_1") (pintype "passive"))
    )
    (net (code "42") (name "Net-(IC1A--IN)") (class "Default")
      (node (ref "IC1") (pin "2") (pinfunction "-IN_2") (pintype "input"))
      (node (ref "R67") (pin "2") (pinfunction "2_2") (pintype "passive"))
      (node (ref "R78") (pin "1") (pinfunction "1_1") (pintype "passive"))
    )
    (net (code "43") (name "Net-(IC1B--IN)") (class "Default")
      (node (ref "IC1") (pin "6") (pinfunction "-IN_6") (pintype "input"))
      (node (ref "R69") (pin "2") (pinfunction "2_2") (pintype "passive"))
      (node (ref "R79") (pin "1") (pinfunction "1_1") (pintype "passive"))
    )
    (net (code "44") (name "Net-(IC1C-+IN)") (class "Default")
      (node (ref "IC1") (pin "10") (pinfunction "+IN_10") (pintype "input"))
      (node (ref "R72") (pin "2") (pinfunction "2_2") (pintype "passive"))
    )
    (net (code "45") (name "Net-(IC1C--IN)") (class "Default")
      (node (ref "IC1") (pin "8") (pinfunction "OUT_8") (pintype "output"))
      (node (ref "IC1") (pin "9") (pinfunction "-IN_9") (pintype "input"))
      (node (ref "R76") (pin "1") (pinfunction "1_1") (pintype "passive"))
    )
    (net (code "46") (name "Net-(IC1D-+IN)") (class "Default")
      (node (ref "IC1") (pin "12") (pinfunction "+IN_12") (pintype "input"))
      (node (ref "R73") (pin "2") (pinfunction "2_2") (pintype "passive"))
    )
    (net (code "47") (name "Net-(IC1D--IN)") (class "Default")
      (node (ref "IC1") (pin "13") (pinfunction "-IN_13") (pintype "input"))
      (node (ref "IC1") (pin "14") (pinfunction "OUT_14") (pintype "output"))
      (node (ref "R74") (pin "1") (pinfunction "1_1") (pintype "passive"))
    )
    (net (code "48") (name "Net-(LM317_3V3-ADJ)") (class "Default")
      (node (ref "LM317_3V3") (pin "1") (pinfunction "ADJ_1") (pintype "input"))
      (node (ref "R80") (pin "1") (pinfunction "1_1") (pintype "passive"))
      (node (ref "R81") (pin "2") (pinfunction "2_2") (pintype "passive"))
    )
    (net (code "49") (name "Net-(LM317_3V3-IN)") (class "Default")
      (node (ref "7805") (pin "IN") (pinfunction "IN_IN") (pintype "input"))
      (node (ref "C13") (pin "1") (pinfunction "1_1") (pintype "passive"))
      (node (ref "C14") (pin "1") (pinfunction "1_1") (pintype "passive"))
      (node (ref "LM317_3V3") (pin "3") (pinfunction "IN_3") (pintype "input"))
      (node (ref "X19") (pin "1") (pinfunction "KL_1") (pintype "passive"))
    )
    (net (code "50") (name "Net-(OK1-A)") (class "Default")
      (node (ref "OK1") (pin "1") (pinfunction "A_1") (pintype "passive"))
      (node (ref "R2") (pin "1") (pinfunction "1_1") (pintype "passive"))
    )
    (net (code "51") (name "Net-(OK1-C)") (class "Default")
      (node (ref "OK1") (pin "2") (pinfunction "C_2") (pintype "passive"))
      (node (ref "T1") (pin "C") (pinfunction "C_C") (pintype "passive"))
    )
    (net (code "52") (name "Net-(OK1-COL)") (class "Default")
      (node (ref "J_POW") (pin "1") (pinfunction "1_1") (pintype "passive"))
      (node (ref "OK1") (pin "4") (pinfunction "COL_4") (pintype "passive"))
      (node (ref "X2") (pin "1") (pinfunction "KL_1") (pintype "passive"))
    )
    (net (code "53") (name "Net-(OK2-A)") (class "Default")
      (node (ref "OK2") (pin "1") (pinfunction "A_1") (pintype "passive"))
      (node (ref "R5") (pin "1") (pinfunction "1_1") (pintype "passive"))
    )
    (net (code "54") (name "Net-(OK2-C)") (class "Default")
      (node (ref "OK2") (pin "2") (pinfunction "C_2") (pintype "passive"))
      (node (ref "T2") (pin "C") (pinfunction "C_C") (pintype "passive"))
    )
    (net (code "55") (name "Net-(OK2-COL)") (class "Default")
      (node (ref "J_POW") (pin "2") (pinfunction "2_2") (pintype "passive"))
      (node (ref "J_POW1") (pin "1") (pinfunction "1_1") (pintype "passive"))
      (node (ref "OK2") (pin "4") (pinfunction "COL_4") (pintype "passive"))
      (node (ref "X3") (pin "1") (pinfunction "KL_1") (pintype "passive"))
    )
    (net (code "56") (name "Net-(OK3-A)") (class "Default")
      (node (ref "OK3") (pin "1") (pinfunction "A_1") (pintype "passive"))
      (node (ref "R8") (pin "1") (pinfunction "1_1") (pintype "passive"))
    )
    (net (code "57") (name "Net-(OK3-C)") (class "Default")
      (node (ref "OK3") (pin "2") (pinfunction "C_2") (pintype "passive"))
      (node (ref "T3") (pin "C") (pinfunction "C_C") (pintype "passive"))
    )
    (net (code "58") (name "Net-(OK3-COL)") (class "Default")
      (node (ref "J_POW1") (pin "2") (pinfunction "2_2") (pintype "passive"))
      (node (ref "J_POW2") (pin "1") (pinfunction "1_1") (pintype "passive"))
      (node (ref "OK3") (pin "4") (pinfunction "COL_4") (pintype "passive"))
      (node (ref "X4") (pin "1") (pinfunction "KL_1") (pintype "passive"))
    )
    (net (code "59") (name "Net-(OK4-A)") (class "Default")
      (node (ref "OK4") (pin "1") (pinfunction "A_1") (pintype "passive"))
      (node (ref "R11") (pin "1") (pinfunction "1_1") (pintype "passive"))
    )
    (net (code "60") (name "Net-(OK4-C)") (class "Default")
      (node (ref "OK4") (pin "2") (pinfunction "C_2") (pintype "passive"))
      (node (ref "T4") (pin "C") (pinfunction "C_C") (pintype "passive"))
    )
    (net (code "61") (name "Net-(OK4-COL)") (class "Default")
      (node (ref "J_POW2") (pin "2") (pinfunction "2_2") (pintype "passive"))
      (node (ref "J_POW3") (pin "1") (pinfunction "1_1") (pintype "passive"))
      (node (ref "OK4") (pin "4") (pinfunction "COL_4") (pintype "passive"))
      (node (ref "X5") (pin "1") (pinfunction "KL_1") (pintype "passive"))
    )
    (net (code "62") (name "Net-(OK5-A)") (class "Default")
      (node (ref "OK5") (pin "1") (pinfunction "A_1") (pintype "passive"))
      (node (ref "R15") (pin "1") (pinfunction "1_1") (pintype "passive"))
    )
    (net (code "63") (name "Net-(OK5-C)") (class "Default")
      (node (ref "OK5") (pin "2") (pinfunction "C_2") (pintype "passive"))
      (node (ref "T5") (pin "C") (pinfunction "C_C") (pintype "passive"))
    )
    (net (code "64") (name "Net-(OK5-COL)") (class "Default")
      (node (ref "J_POW7") (pin "1") (pinfunction "1_1") (pintype "passive"))
      (node (ref "OK5") (pin "4") (pinfunction "COL_4") (pintype "passive"))
      (node (ref "X9") (pin "1") (pinfunction "KL_1") (pintype "passive"))
    )
    (net (code "65") (name "Net-(OK6-A)") (class "Default")
      (node (ref "OK6") (pin "1") (pinfunction "A_1") (pintype "passive"))
      (node (ref "R18") (pin "1") (pinfunction "1_1") (pintype "passive"))
    )
    (net (code "66") (name "Net-(OK6-C)") (class "Default")
      (node (ref "OK6") (pin "2") (pinfunction "C_2") (pintype "passive"))
      (node (ref "T6") (pin "C") (pinfunction "C_C") (pintype "passive"))
    )
    (net (code "67") (name "Net-(OK6-COL)") (class "Default")
      (node (ref "J_POW6") (pin "1") (pinfunction "1_1") (pintype "passive"))
      (node (ref "J_POW7") (pin "2") (pinfunction "2_2") (pintype "passive"))
      (node (ref "OK6") (pin "4") (pinfunction "COL_4") (pintype "passive"))
      (node (ref "X8") (pin "1") (pinfunction "KL_1") (pintype "passive"))
    )
    (net (code "68") (name "Net-(OK7-A)") (class "Default")
      (node (ref "OK7") (pin "1") (pinfunction "A_1") (pintype "passive"))
      (node (ref "R21") (pin "1") (pinfunction "1_1") (pintype "passive"))
    )
    (net (code "69") (name "Net-(OK7-C)") (class "Default")
      (node (ref "OK7") (pin "2") (pinfunction "C_2") (pintype "passive"))
      (node (ref "T7") (pin "C") (pinfunction "C_C") (pintype "passive"))
    )
    (net (code "70") (name "Net-(OK7-COL)") (class "Default")
      (node (ref "J_POW5") (pin "1") (pinfunction "1_1") (pintype "passive"))
      (node (ref "J_POW6") (pin "2") (pinfunction "2_2") (pintype "passive"))
      (node (ref "OK7") (pin "4") (pinfunction "COL_4") (pintype "passive"))
      (node (ref "X7") (pin "1") (pinfunction "KL_1") (pintype "passive"))
    )
    (net (code "71") (name "Net-(OK8-A)") (class "Default")
      (node (ref "OK8") (pin "1") (pinfunction "A_1") (pintype "passive"))
      (node (ref "R24") (pin "1") (pinfunction "1_1") (pintype "passive"))
    )
    (net (code "72") (name "Net-(OK8-C)") (class "Default")
      (node (ref "OK8") (pin "2") (pinfunction "C_2") (pintype "passive"))
      (node (ref "T8") (pin "C") (pinfunction "C_C") (pintype "passive"))
    )
    (net (code "73") (name "Net-(OK8-COL)") (class "Default")
      (node (ref "J_POW3") (pin "2") (pinfunction "2_2") (pintype "passive"))
      (node (ref "J_POW5") (pin "2") (pinfunction "2_2") (pintype "passive"))
      (node (ref "OK8") (pin "4") (pinfunction "COL_4") (pintype "passive"))
      (node (ref "X6") (pin "1") (pinfunction "KL_1") (pintype "passive"))
    )
    (net (code "74") (name "Net-(OK9-A)") (class "Default")
      (node (ref "OK9") (pin "1") (pinfunction "A_1") (pintype "passive"))
      (node (ref "R14") (pin "1") (pinfunction "1_1") (pintype "passive"))
      (node (ref "R27") (pin "2") (pinfunction "2_2") (pintype "passive"))
    )
    (net (code "75") (name "Net-(OK9-C)") (class "Default")
      (node (ref "OK9") (pin "2") (pinfunction "C_2") (pintype "passive"))
      (node (ref "Q1") (pin "C") (pinfunction "C_C") (pintype "passive"))
    )
    (net (code "76") (name "Net-(OK10-A)") (class "Default")
      (node (ref "OK10") (pin "1") (pinfunction "A_1") (pintype "passive"))
      (node (ref "R30") (pin "1") (pinfunction "1_1") (pintype "passive"))
      (node (ref "R31") (pin "2") (pinfunction "2_2") (pintype "passive"))
    )
    (net (code "77") (name "Net-(OK10-C)") (class "Default")
      (node (ref "OK10") (pin "2") (pinfunction "C_2") (pintype "passive"))
      (node (ref "Q2") (pin "C") (pinfunction "C_C") (pintype "passive"))
    )
    (net (code "78") (name "Net-(OK11-A)") (class "Default")
      (node (ref "OK11") (pin "1") (pinfunction "A_1") (pintype "passive"))
      (node (ref "R34") (pin "1") (pinfunction "1_1") (pintype "passive"))
      (node (ref "R35") (pin "2") (pinfunction "2_2") (pintype "passive"))
    )
    (net (code "79") (name "Net-(OK11-C)") (class "Default")
      (node (ref "OK11") (pin "2") (pinfunction "C_2") (pintype "passive"))
      (node (ref "Q3") (pin "C") (pinfunction "C_C") (pintype "passive"))
    )
    (net (code "80") (name "Net-(OK12-A)") (class "Default")
      (node (ref "OK12") (pin "1") (pinfunction "A_1") (pintype "passive"))
      (node (ref "R38") (pin "1") (pinfunction "1_1") (pintype "passive"))
      (node (ref "R39") (pin "2") (pinfunction "2_2") (pintype "passive"))
    )
    (net (code "81") (name "Net-(OK12-C)") (class "Default")
      (node (ref "OK12") (pin "2") (pinfunction "C_2") (pintype "passive"))
      (node (ref "Q4") (pin "C") (pinfunction "C_C") (pintype "passive"))
    )
    (net (code "82") (name "Net-(OK13-A)") (class "Default")
      (node (ref "OK13") (pin "1") (pinfunction "A_1") (pintype "passive"))
      (node (ref "R42") (pin "1") (pinfunction "1_1") (pintype "passive"))
    )
    (net (code "83") (name "Net-(OK13-C)") (class "Default")
      (node (ref "OK13") (pin "2") (pinfunction "C_2") (pintype "passive"))
      (node (ref "T9") (pin "C") (pinfunction "C_C") (pintype "passive"))
    )
    (net (code "84") (name "Net-(OK13-COL)") (class "Default")
      (node (ref "J_POW10") (pin "1") (pinfunction "1_1") (pintype "passive"))
      (node (ref "OK13") (pin "4") (pinfunction "COL_4") (pintype "passive"))
      (node (ref "X14") (pin "1") (pinfunction "KL_1") (pintype "passive"))
    )
    (net (code "85") (name "Net-(OK13-EMIT)") (class "Default")
      (node (ref "OK13") (pin "3") (pinfunction "EMIT_3") (pintype "passive"))
      (node (ref "R44") (pin "1") (pinfunction "1_1") (pintype "passive"))
      (node (ref "R45") (pin "1") (pinfunction "1_1") (pintype "passive"))
      (node (ref "R46") (pin "1") (pinfunction "1_1") (pintype "passive"))
    )
    (net (code "86") (name "Net-(OK14-A)") (class "Default")
      (node (ref "OK14") (pin "1") (pinfunction "A_1") (pintype "passive"))
      (node (ref "R44") (pin "2") (pinfunction "2_2") (pintype "passive"))
    )
    (net (code "87") (name "Net-(OK14-C)") (class "Default")
      (node (ref "OK14") (pin "2") (pinfunction "C_2") (pintype "passive"))
      (node (ref "T10") (pin "C") (pinfunction "C_C") (pintype "passive"))
    )
    (net (code "88") (name "Net-(OK15-A)") (class "Default")
      (node (ref "OK15") (pin "1") (pinfunction "A_1") (pintype "passive"))
      (node (ref "R48") (pin "1") (pinfunction "1_1") (pintype "passive"))
    )
    (net (code "89") (name "Net-(OK15-C)") (class "Default")
      (node (ref "OK15") (pin "2") (pinfunction "C_2") (pintype "passive"))
      (node (ref "T11") (pin "C") (pinfunction "C_C") (pintype "passive"))
    )
    (net (code "90") (name "Net-(OK15-COL)") (class "Default")
      (node (ref "J_POW10") (pin "2") (pinfunction "2_2") (pintype "passive"))
      (node (ref "J_POW11") (pin "1") (pinfunction "1_1") (pintype "passive"))
      (node (ref "OK15") (pin "4") (pinfunction "COL_4") (pintype "passive"))
      (node (ref "X15") (pin "1") (pinfunction "KL_1") (pintype "passive"))
    )
    (net (code "91") (name "Net-(OK15-EMIT)") (class "Default")
      (node (ref "OK15") (pin "3") (pinfunction "EMIT_3") (pintype "passive"))
      (node (ref "R50") (pin "1") (pinfunction "1_1") (pintype "passive"))
      (node (ref "R51") (pin "1") (pinfunction "1_1") (pintype "passive"))
      (node (ref "R52") (pin "1") (pinfunction "1_1") (pintype "passive"))
    )
    (net (code "92") (name "Net-(OK16-A)") (class "Default")
      (node (ref "OK16") (pin "1") (pinfunction "A_1") (pintype "passive"))
      (node (ref "R50") (pin "2") (pinfunction "2_2") (pintype "passive"))
    )
    (net (code "93") (name "Net-(OK16-C)") (class "Default")
      (node (ref "OK16") (pin "2") (pinfunction "C_2") (pintype "passive"))
      (node (ref "T12") (pin "C") (pinfunction "C_C") (pintype "passive"))
    )
    (net (code "94") (name "Net-(OK17-A)") (class "Default")
      (node (ref "OK17") (pin "1") (pinfunction "A_1") (pintype "passive"))
      (node (ref "R54") (pin "1") (pinfunction "1_1") (pintype "passive"))
    )
    (net (code "95") (name "Net-(OK17-C)") (class "Default")
      (node (ref "OK17") (pin "2") (pinfunction "C_2") (pintype "passive"))
      (node (ref "T13") (pin "C") (pinfunction "C_C") (pintype "passive"))
    )
    (net (code "96") (name "Net-(OK17-COL)") (class "Default")
      (node (ref "J_POW11") (pin "2") (pinfunction "2_2") (pintype "passive"))
      (node (ref "J_POW13") (pin "1") (pinfunction "1_1") (pintype "passive"))
      (node (ref "OK17") (pin "4") (pinfunction "COL_4") (pintype "passive"))
      (node (ref "X17") (pin "1") (pinfunction "KL_1") (pintype "passive"))
    )
    (net (code "97") (name "Net-(OK17-EMIT)") (class "Default")
      (node (ref "OK17") (pin "3") (pinfunction "EMIT_3") (pintype "passive"))
      (node (ref "R56") (pin "1") (pinfunction "1_1") (pintype "passive"))
      (node (ref "R57") (pin "1") (pinfunction "1_1") (pintype "passive"))
      (node (ref "R58") (pin "1") (pinfunction "1_1") (pintype "passive"))
    )
    (net (code "98") (name "Net-(OK18-A)") (class "Default")
      (node (ref "OK18") (pin "1") (pinfunction "A_1") (pintype "passive"))
      (node (ref "R56") (pin "2") (pinfunction "2_2") (pintype "passive"))
    )
    (net (code "99") (name "Net-(OK18-C)") (class "Default")
      (node (ref "OK18") (pin "2") (pinfunction "C_2") (pintype "passive"))
      (node (ref "T14") (pin "C") (pinfunction "C_C") (pintype "passive"))
    )
    (net (code "100") (name "Net-(OK19-A)") (class "Default")
      (node (ref "OK19") (pin "1") (pinfunction "A_1") (pintype "passive"))
      (node (ref "R60") (pin "1") (pinfunction "1_1") (pintype "passive"))
    )
    (net (code "101") (name "Net-(OK19-C)") (class "Default")
      (node (ref "OK19") (pin "2") (pinfunction "C_2") (pintype "passive"))
      (node (ref "T15") (pin "C") (pinfunction "C_C") (pintype "passive"))
    )
    (net (code "102") (name "Net-(OK19-COL)") (class "Default")
      (node (ref "J_POW13") (pin "2") (pinfunction "2_2") (pintype "passive"))
      (node (ref "OK19") (pin "4") (pinfunction "COL_4") (pintype "passive"))
      (node (ref "X16") (pin "1") (pinfunction "KL_1") (pintype "passive"))
    )
    (net (code "103") (name "Net-(OK19-EMIT)") (class "Default")
      (node (ref "OK19") (pin "3") (pinfunction "EMIT_3") (pintype "passive"))
      (node (ref "R62") (pin "1") (pinfunction "1_1") (pintype "passive"))
      (node (ref "R63") (pin "1") (pinfunction "1_1") (pintype "passive"))
      (node (ref "R64") (pin "1") (pinfunction "1_1") (pintype "passive"))
    )
    (net (code "104") (name "Net-(OK20-A)") (class "Default")
      (node (ref "OK20") (pin "1") (pinfunction "A_1") (pintype "passive"))
      (node (ref "R62") (pin "2") (pinfunction "2_2") (pintype "passive"))
    )
    (net (code "105") (name "Net-(OK20-C)") (class "Default")
      (node (ref "OK20") (pin "2") (pinfunction "C_2") (pintype "passive"))
      (node (ref "T16") (pin "C") (pinfunction "C_C") (pintype "passive"))
    )
    (net (code "106") (name "Net-(Q1-PadB)") (class "Default")
      (node (ref "Q1") (pin "B") (pinfunction "B_B") (pintype "passive"))
      (node (ref "R28") (pin "1") (pinfunction "1_1") (pintype "passive"))
    )
    (net (code "107") (name "Net-(Q2-PadB)") (class "Default")
      (node (ref "Q2") (pin "B") (pinfunction "B_B") (pintype "passive"))
      (node (ref "R32") (pin "1") (pinfunction "1_1") (pintype "passive"))
    )
    (net (code "108") (name "Net-(Q3-PadB)") (class "Default")
      (node (ref "Q3") (pin "B") (pinfunction "B_B") (pintype "passive"))
      (node (ref "R36") (pin "1") (pinfunction "1_1") (pintype "passive"))
    )
    (net (code "109") (name "Net-(Q4-PadB)") (class "Default")
      (node (ref "Q4") (pin "B") (pinfunction "B_B") (pintype "passive"))
      (node (ref "R40") (pin "1") (pinfunction "1_1") (pintype "passive"))
    )
    (net (code "110") (name "Net-(R4-Pad1)") (class "Default")
      (node (ref "R4") (pin "1") (pinfunction "1_1") (pintype "passive"))
      (node (ref "T1") (pin "B") (pinfunction "B_B") (pintype "passive"))
    )
    (net (code "111") (name "Net-(R7-Pad1)") (class "Default")
      (node (ref "R7") (pin "1") (pinfunction "1_1") (pintype "passive"))
      (node (ref "T2") (pin "B") (pinfunction "B_B") (pintype "passive"))
    )
    (net (code "112") (name "Net-(R10-Pad1)") (class "Default")
      (node (ref "R10") (pin "1") (pinfunction "1_1") (pintype "passive"))
      (node (ref "T3") (pin "B") (pinfunction "B_B") (pintype "passive"))
    )
    (net (code "113") (name "Net-(R13-Pad1)") (class "Default")
      (node (ref "R13") (pin "1") (pinfunction "1_1") (pintype "passive"))
      (node (ref "T4") (pin "B") (pinfunction "B_B") (pintype "passive"))
    )
    (net (code "114") (name "Net-(R17-Pad1)") (class "Default")
      (node (ref "R17") (pin "1") (pinfunction "1_1") (pintype "passive"))
      (node (ref "T5") (pin "B") (pinfunction "B_B") (pintype "passive"))
    )
    (net (code "115") (name "Net-(R20-Pad1)") (class "Default")
      (node (ref "R20") (pin "1") (pinfunction "1_1") (pintype "passive"))
      (node (ref "T6") (pin "B") (pinfunction "B_B") (pintype "passive"))
    )
    (net (code "116") (name "Net-(R23-Pad1)") (class "Default")
      (node (ref "R23") (pin "1") (pinfunction "1_1") (pintype "passive"))
      (node (ref "T7") (pin "B") (pinfunction "B_B") (pintype "passive"))
    )
    (net (code "117") (name "Net-(R26-Pad1)") (class "Default")
      (node (ref "R26") (pin "1") (pinfunction "1_1") (pintype "passive"))
      (node (ref "T8") (pin "B") (pinfunction "B_B") (pintype "passive"))
    )
    (net (code "118") (name "Net-(R43-Pad1)") (class "Default")
      (node (ref "R43") (pin "1") (pinfunction "1_1") (pintype "passive"))
      (node (ref "T9") (pin "B") (pinfunction "B_B") (pintype "passive"))
    )
    (net (code "119") (name "Net-(R45-Pad2)") (class "Default")
      (node (ref "R45") (pin "2") (pinfunction "2_2") (pintype "passive"))
      (node (ref "T10") (pin "B") (pinfunction "B_B") (pintype "passive"))
    )
    (net (code "120") (name "Net-(R49-Pad1)") (class "Default")
      (node (ref "R49") (pin "1") (pinfunction "1_1") (pintype "passive"))
      (node (ref "T11") (pin "B") (pinfunction "B_B") (pintype "passive"))
    )
    (net (code "121") (name "Net-(R51-Pad2)") (class "Default")
      (node (ref "R51") (pin "2") (pinfunction "2_2") (pintype "passive"))
      (node (ref "T12") (pin "B") (pinfunction "B_B") (pintype "passive"))
    )
    (net (code "122") (name "Net-(R55-Pad1)") (class "Default")
      (node (ref "R55") (pin "1") (pinfunction "1_1") (pintype "passive"))
      (node (ref "T13") (pin "B") (pinfunction "B_B") (pintype "passive"))
    )
    (net (code "123") (name "Net-(R57-Pad2)") (class "Default")
      (node (ref "R57") (pin "2") (pinfunction "2_2") (pintype "passive"))
      (node (ref "T14") (pin "B") (pinfunction "B_B") (pintype "passive"))
    )
    (net (code "124") (name "Net-(R61-Pad1)") (class "Default")
      (node (ref "R61") (pin "1") (pinfunction "1_1") (pintype "passive"))
      (node (ref "T15") (pin "B") (pinfunction "B_B") (pintype "passive"))
    )
    (net (code "125") (name "Net-(R63-Pad2)") (class "Default")
      (node (ref "R63") (pin "2") (pinfunction "2_2") (pintype "passive"))
      (node (ref "T16") (pin "B") (pinfunction "B_B") (pintype "passive"))
    )
    (net (code "126") (name "Net-(R66-Pad1)") (class "Default")
      (node (ref "R66") (pin "1") (pinfunction "1_1") (pintype "passive"))
      (node (ref "R78") (pin "2") (pinfunction "2_2") (pintype "passive"))
    )
    (net (code "127") (name "Net-(R68-Pad1)") (class "Default")
      (node (ref "R68") (pin "1") (pinfunction "1_1") (pintype "passive"))
      (node (ref "R79") (pin "2") (pinfunction "2_2") (pintype "passive"))
    )
    (net (code "128") (name "Net-(X2C-KL)") (class "Default")
      (node (ref "J_GND") (pin "1") (pinfunction "1_1") (pintype "passive"))
      (node (ref "R3") (pin "1") (pinfunction "1_1") (pintype "passive"))
      (node (ref "X2") (pin "3") (pinfunction "KL_3") (pintype "passive"))
    )
    (net (code "129") (name "Net-(X3C-KL)") (class "Default")
      (node (ref "J_GND") (pin "2") (pinfunction "2_2") (pintype "passive"))
      (node (ref "J_GND1") (pin "1") (pinfunction "1_1") (pintype "passive"))
      (node (ref "R6") (pin "1") (pinfunction "1_1") (pintype "passive"))
      (node (ref "X3") (pin "3") (pinfunction "KL_3") (pintype "passive"))
    )
    (net (code "130") (name "Net-(X4C-KL)") (class "Default")
      (node (ref "J_GND1") (pin "2") (pinfunction "2_2") (pintype "passive"))
      (node (ref "J_GND2") (pin "1") (pinfunction "1_1") (pintype "passive"))
      (node (ref "R9") (pin "1") (pinfunction "1_1") (pintype "passive"))
      (node (ref "X4") (pin "3") (pinfunction "KL_3") (pintype "passive"))
    )
    (net (code "131") (name "Net-(X5C-KL)") (class "Default")
      (node (ref "J_GND2") (pin "2") (pinfunction "2_2") (pintype "passive"))
      (node (ref "J_GND3") (pin "1") (pinfunction "1_1") (pintype "passive"))
      (node (ref "R12") (pin "1") (pinfunction "1_1") (pintype "passive"))
      (node (ref "X5") (pin "3") (pinfunction "KL_3") (pintype "passive"))
    )
    (net (code "132") (name "Net-(X6C-KL)") (class "Default")
      (node (ref "J_GND3") (pin "2") (pinfunction "2_2") (pintype "passive"))
      (node (ref "J_GND5") (pin "2") (pinfunction "2_2") (pintype "passive"))
      (node (ref "R25") (pin "1") (pinfunction "1_1") (pintype "passive"))
      (node (ref "X6") (pin "3") (pinfunction "KL_3") (pintype "passive"))
    )
    (net (code "133") (name "Net-(X7C-KL)") (class "Default")
      (node (ref "J_GND5") (pin "1") (pinfunction "1_1") (pintype "passive"))
      (node (ref "J_GND6") (pin "2") (pinfunction "2_2") (pintype "passive"))
      (node (ref "R22") (pin "1") (pinfunction "1_1") (pintype "passive"))
      (node (ref "X7") (pin "3") (pinfunction "KL_3") (pintype "passive"))
    )
    (net (code "134") (name "Net-(X8C-KL)") (class "Default")
      (node (ref "J_GND6") (pin "1") (pinfunction "1_1") (pintype "passive"))
      (node (ref "J_GND7") (pin "2") (pinfunction "2_2") (pintype "passive"))
      (node (ref "R19") (pin "1") (pinfunction "1_1") (pintype "passive"))
      (node (ref "X8") (pin "3") (pinfunction "KL_3") (pintype "passive"))
    )
    (net (code "135") (name "Net-(X9C-KL)") (class "Default")
      (node (ref "J_GND7") (pin "1") (pinfunction "1_1") (pintype "passive"))
      (node (ref "R16") (pin "1") (pinfunction "1_1") (pintype "passive"))
      (node (ref "X9") (pin "3") (pinfunction "KL_3") (pintype "passive"))
    )
    (net (code "136") (name "Net-(X10A-KL)") (class "Default")
      (node (ref "J_POW4") (pin "1") (pinfunction "1_1") (pintype "passive"))
      (node (ref "R14") (pin "2") (pinfunction "2_2") (pintype "passive"))
      (node (ref "R27") (pin "1") (pinfunction "1_1") (pintype "passive"))
      (node (ref "X10") (pin "1") (pinfunction "KL_1") (pintype "passive"))
    )
    (net (code "137") (name "Net-(X10C-KL)") (class "Default")
      (node (ref "J_GND4") (pin "1") (pinfunction "1_1") (pintype "passive"))
      (node (ref "Q1") (pin "E") (pinfunction "E_E") (pintype "passive"))
      (node (ref "X10") (pin "3") (pinfunction "KL_3") (pintype "passive"))
    )
    (net (code "138") (name "Net-(X11A-KL)") (class "Default")
      (node (ref "J_POW4") (pin "2") (pinfunction "2_2") (pintype "passive"))
      (node (ref "J_POW8") (pin "1") (pinfunction "1_1") (pintype "passive"))
      (node (ref "R30") (pin "2") (pinfunction "2_2") (pintype "passive"))
      (node (ref "R31") (pin "1") (pinfunction "1_1") (pintype "passive"))
      (node (ref "X11") (pin "1") (pinfunction "KL_1") (pintype "passive"))
    )
    (net (code "139") (name "Net-(X11C-KL)") (class "Default")
      (node (ref "J_GND4") (pin "2") (pinfunction "2_2") (pintype "passive"))
      (node (ref "J_GND8") (pin "1") (pinfunction "1_1") (pintype "passive"))
      (node (ref "Q2") (pin "E") (pinfunction "E_E") (pintype "passive"))
      (node (ref "X11") (pin "3") (pinfunction "KL_3") (pintype "passive"))
    )
    (net (code "140") (name "Net-(X12A-KL)") (class "Default")
      (node (ref "J_POW8") (pin "2") (pinfunction "2_2") (pintype "passive"))
      (node (ref "J_POW9") (pin "1") (pinfunction "1_1") (pintype "passive"))
      (node (ref "R34") (pin "2") (pinfunction "2_2") (pintype "passive"))
      (node (ref "R35") (pin "1") (pinfunction "1_1") (pintype "passive"))
      (node (ref "X12") (pin "1") (pinfunction "KL_1") (pintype "passive"))
    )
    (net (code "141") (name "Net-(X12C-KL)") (class "Default")
      (node (ref "J_GND8") (pin "2") (pinfunction "2_2") (pintype "passive"))
      (node (ref "J_GND9") (pin "1") (pinfunction "1_1") (pintype "passive"))
      (node (ref "Q3") (pin "E") (pinfunction "E_E") (pintype "passive"))
      (node (ref "X12") (pin "3") (pinfunction "KL_3") (pintype "passive"))
    )
    (net (code "142") (name "Net-(X13A-KL)") (class "Default")
      (node (ref "J_POW9") (pin "2") (pinfunction "2_2") (pintype "passive"))
      (node (ref "R38") (pin "2") (pinfunction "2_2") (pintype "passive"))
      (node (ref "R39") (pin "1") (pinfunction "1_1") (pintype "passive"))
      (node (ref "X13") (pin "1") (pinfunction "KL_1") (pintype "passive"))
    )
    (net (code "143") (name "Net-(X13C-KL)") (class "Default")
      (node (ref "J_GND9") (pin "2") (pinfunction "2_2") (pintype "passive"))
      (node (ref "Q4") (pin "E") (pinfunction "E_E") (pintype "passive"))
      (node (ref "X13") (pin "3") (pinfunction "KL_3") (pintype "passive"))
    )
    (net (code "144") (name "Net-(X14C-KL)") (class "Default")
      (node (ref "J_GND10") (pin "1") (pinfunction "1_1") (pintype "passive"))
      (node (ref "T10") (pin "E") (pinfunction "E_E") (pintype "passive"))
      (node (ref "X14") (pin "3") (pinfunction "KL_3") (pintype "passive"))
    )
    (net (code "145") (name "Net-(X15C-KL)") (class "Default")
      (node (ref "J_GND10") (pin "2") (pinfunction "2_2") (pintype "passive"))
      (node (ref "J_GND11") (pin "1") (pinfunction "1_1") (pintype "passive"))
      (node (ref "T12") (pin "E") (pinfunction "E_E") (pintype "passive"))
      (node (ref "X15") (pin "3") (pinfunction "KL_3") (pintype "passive"))
    )
    (net (code "146") (name "Net-(X16C-KL)") (class "Default")
      (node (ref "J_GND13") (pin "2") (pinfunction "2_2") (pintype "passive"))
      (node (ref "T16") (pin "E") (pinfunction "E_E") (pintype "passive"))
      (node (ref "X16") (pin "3") (pinfunction "KL_3") (pintype "passive"))
    )
    (net (code "147") (name "Net-(X17C-KL)") (class "Default")
      (node (ref "J_GND11") (pin "2") (pinfunction "2_2") (pintype "passive"))
      (node (ref "J_GND13") (pin "1") (pinfunction "1_1") (pintype "passive"))
      (node (ref "T14") (pin "E") (pinfunction "E_E") (pintype "passive"))
      (node (ref "X17") (pin "3") (pinfunction "KL_3") (pintype "passive"))
    )
    (net (code "148") (name "Net-(X18A-KL)") (class "Default")
      (node (ref "AC2") (pin "MP") (pinfunction "MP_MP") (pintype "passive"))
      (node (ref "X18") (pin "1") (pinfunction "KL_1") (pintype "passive"))
    )
    (net (code "149") (name "Net-(X18B-KL)") (class "Default")
      (node (ref "AC1") (pin "MP") (pinfunction "MP_MP") (pintype "passive"))
      (node (ref "X18") (pin "2") (pinfunction "KL_2") (pintype "passive"))
    )
    (net (code "150") (name "OUT_0") (class "Default")
      (node (ref "OK1") (pin "3") (pinfunction "EMIT_3") (pintype "passive"))
      (node (ref "R3") (pin "2") (pinfunction "2_2") (pintype "passive"))
      (node (ref "X2") (pin "2") (pinfunction "KL_2") (pintype "passive"))
    )
    (net (code "151") (name "OUT_1") (class "Default")
      (node (ref "OK2") (pin "3") (pinfunction "EMIT_3") (pintype "passive"))
      (node (ref "R6") (pin "2") (pinfunction "2_2") (pintype "passive"))
      (node (ref "X3") (pin "2") (pinfunction "KL_2") (pintype "passive"))
    )
    (net (code "152") (name "OUT_2") (class "Default")
      (node (ref "OK3") (pin "3") (pinfunction "EMIT_3") (pintype "passive"))
      (node (ref "R9") (pin "2") (pinfunction "2_2") (pintype "passive"))
      (node (ref "X4") (pin "2") (pinfunction "KL_2") (pintype "passive"))
    )
    (net (code "153") (name "OUT_3") (class "Default")
      (node (ref "OK4") (pin "3") (pinfunction "EMIT_3") (pintype "passive"))
      (node (ref "R12") (pin "2") (pinfunction "2_2") (pintype "passive"))
      (node (ref "X5") (pin "2") (pinfunction "KL_2") (pintype "passive"))
    )
    (net (code "154") (name "OUT_4") (class "Default")
      (node (ref "OK5") (pin "3") (pinfunction "EMIT_3") (pintype "passive"))
      (node (ref "R16") (pin "2") (pinfunction "2_2") (pintype "passive"))
      (node (ref "X9") (pin "2") (pinfunction "KL_2") (pintype "passive"))
    )
    (net (code "155") (name "OUT_5") (class "Default")
      (node (ref "OK6") (pin "3") (pinfunction "EMIT_3") (pintype "passive"))
      (node (ref "R19") (pin "2") (pinfunction "2_2") (pintype "passive"))
      (node (ref "X8") (pin "2") (pinfunction "KL_2") (pintype "passive"))
    )
    (net (code "156") (name "OUT_6") (class "Default")
      (node (ref "OK7") (pin "3") (pinfunction "EMIT_3") (pintype "passive"))
      (node (ref "R22") (pin "2") (pinfunction "2_2") (pintype "passive"))
      (node (ref "X7") (pin "2") (pinfunction "KL_2") (pintype "passive"))
    )
    (net (code "157") (name "OUT_7") (class "Default")
      (node (ref "OK8") (pin "3") (pinfunction "EMIT_3") (pintype "passive"))
      (node (ref "R25") (pin "2") (pinfunction "2_2") (pintype "passive"))
      (node (ref "X6") (pin "2") (pinfunction "KL_2") (pintype "passive"))
    )
    (net (code "158") (name "unconnected-(MALE-Pad24)") (class "Default")
      (node (ref "MALE") (pin "24") (pinfunction "24_24") (pintype "passive"))
    )
    (net (code "159") (name "unconnected-(MALE-Pad26)") (class "Default")
      (node (ref "MALE") (pin "26") (pinfunction "26_26") (pintype "passive"))
    )
    (net (code "160") (name "unconnected-(MALE-Pad28)") (class "Default")
      (node (ref "MALE") (pin "28") (pinfunction "28_28") (pintype "passive"))
    )
    (net (code "161") (name "unconnected-(MALE-Pad29)") (class "Default")
      (node (ref "MALE") (pin "29") (pinfunction "29_29") (pintype "passive"))
    )
    (net (code "162") (name "unconnected-(MALE-Pad30)") (class "Default")
      (node (ref "MALE") (pin "30") (pinfunction "30_30") (pintype "passive"))
    )
    (net (code "163") (name "unconnected-(MALE-Pad31)") (class "Default")
      (node (ref "MALE") (pin "31") (pinfunction "31_31") (pintype "passive"))
    )
    (net (code "164") (name "unconnected-(MALE-Pad32)") (class "Default")
      (node (ref "MALE") (pin "32") (pinfunction "32_32") (pintype "passive"))
    )
  )
)
